# SCH_Photon-Avatar-Headset_2024-04-25.net
KiCad netlist of a schematic drawn in EasyEDA
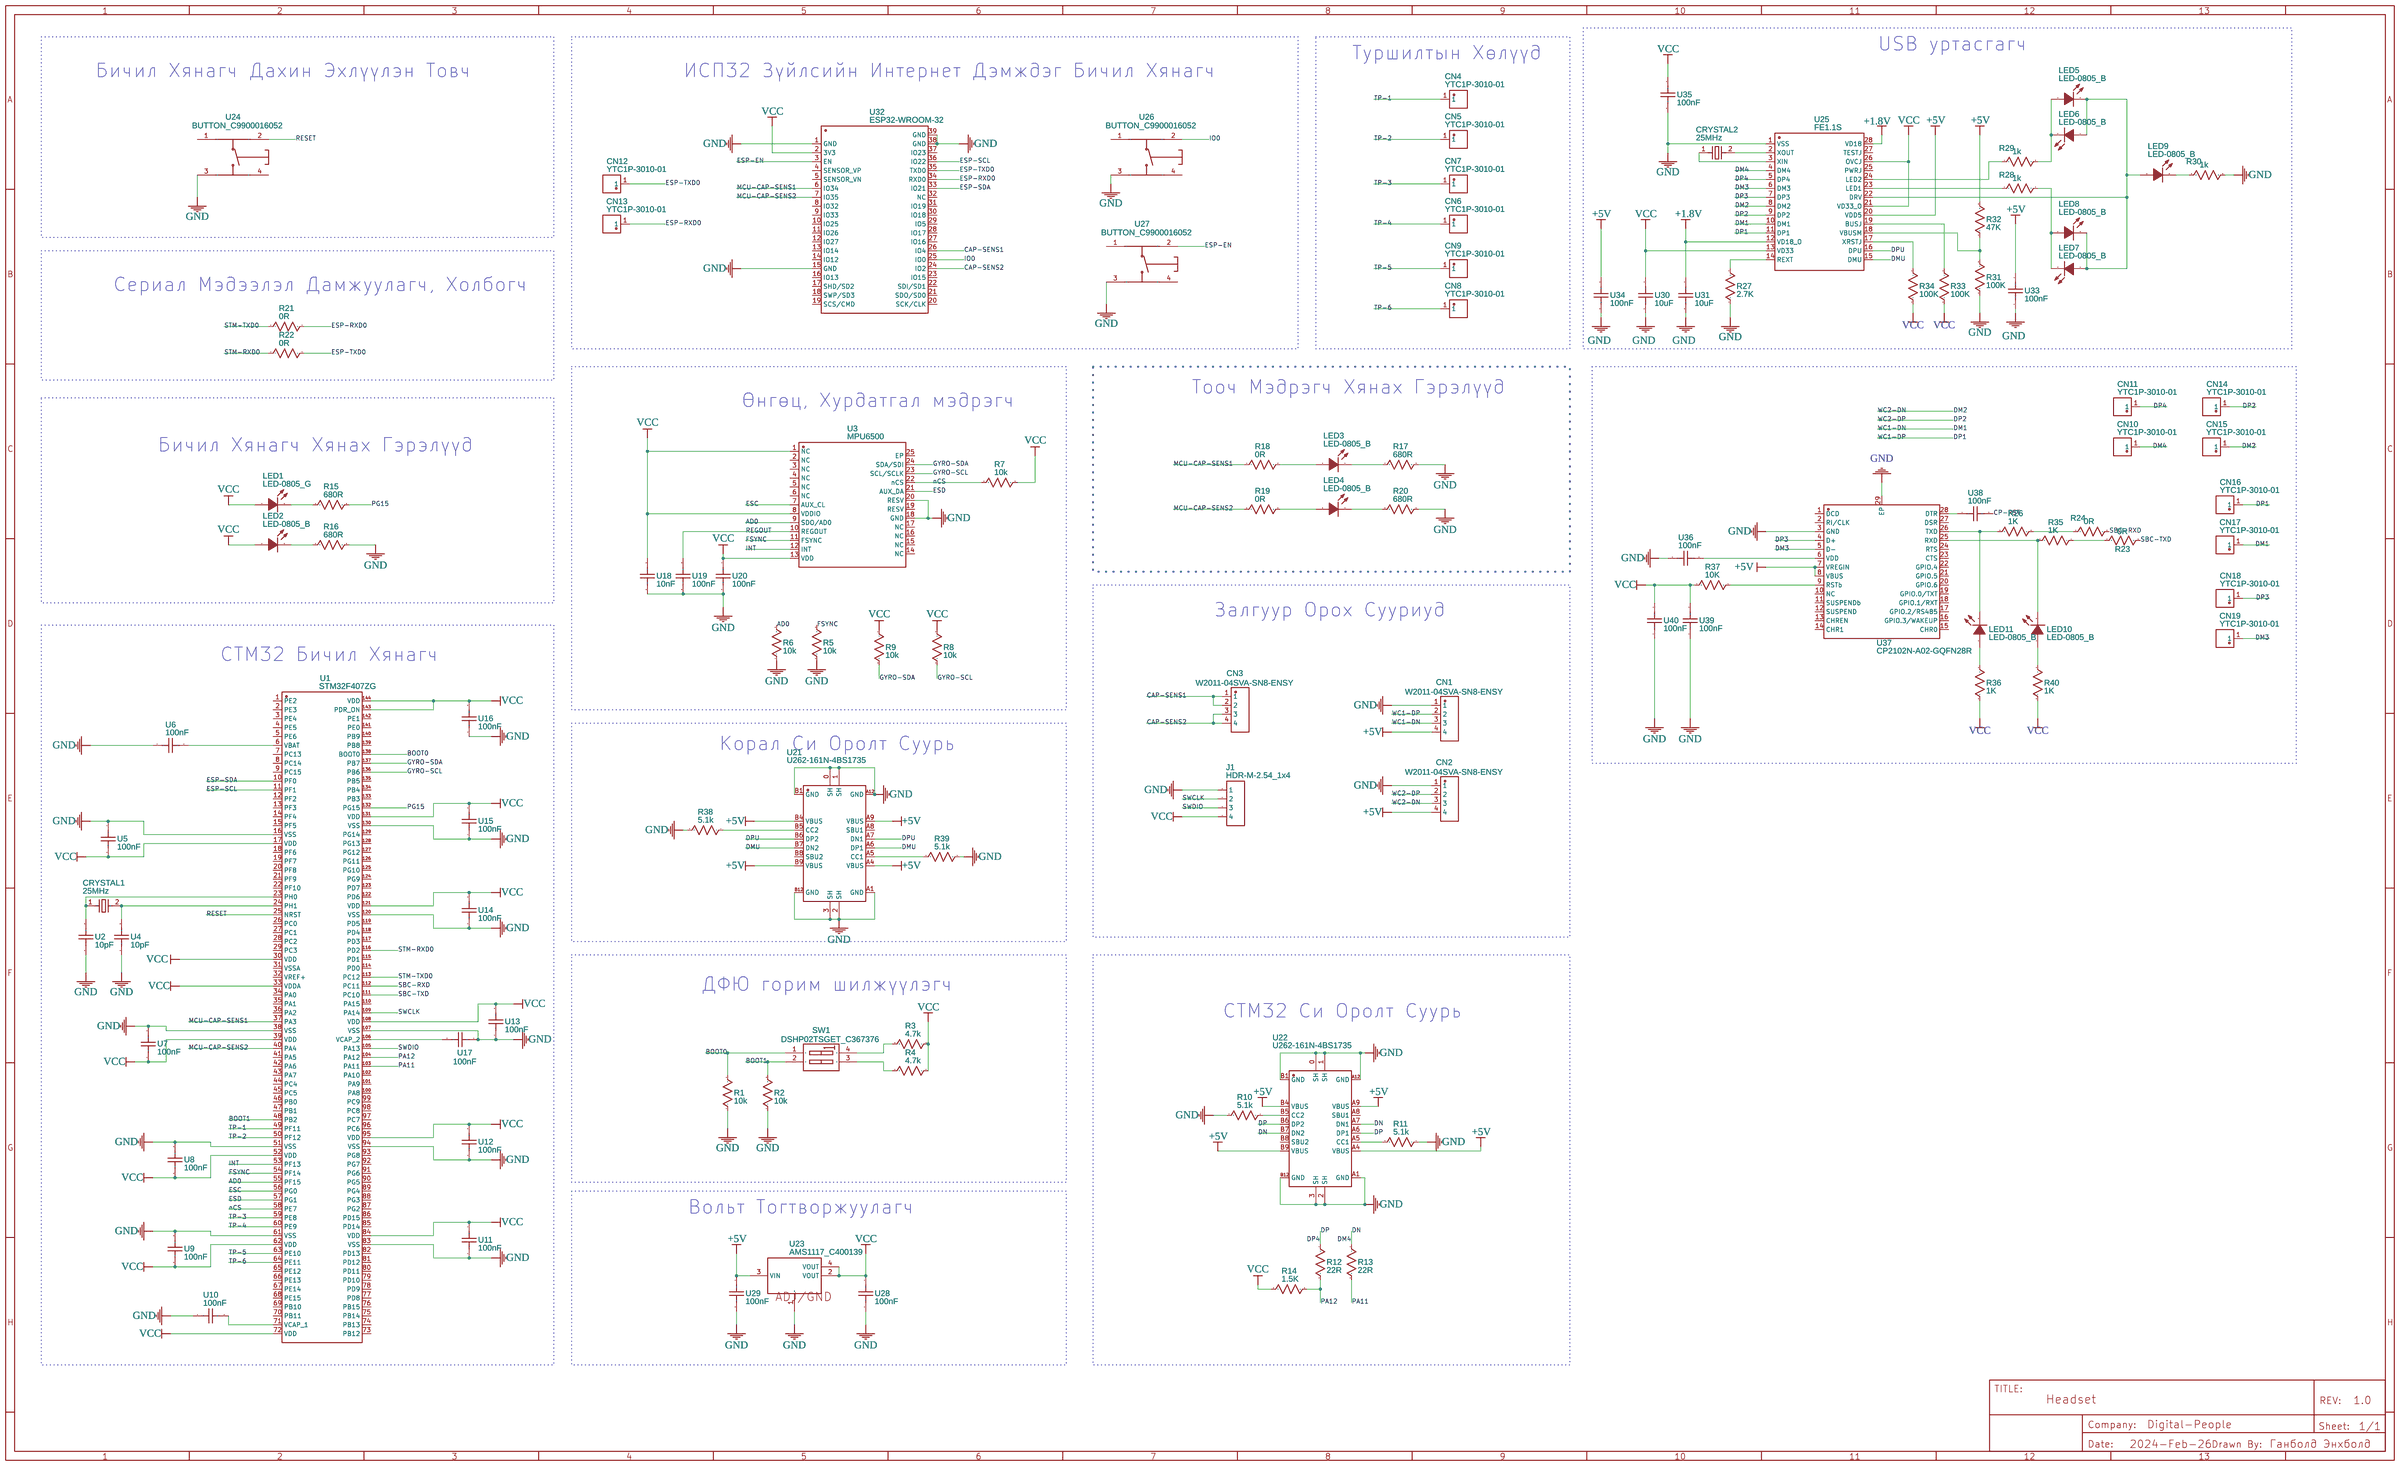
[diagram p0: schematic sheet]

(export (version "E")
  (design (tool "Eeschema 10.0.6"))
  (components
    (comp (ref "CN1") (value "W2011-04SVA-SN8-ENSY") (libsource (lib "") (part "W2011-04SVA-SN8-ENSY")))
    (comp (ref "CN2") (value "W2011-04SVA-SN8-ENSY") (libsource (lib "") (part "W2011-04SVA-SN8-ENSY")))
    (comp (ref "CN3") (value "W2011-04SVA-SN8-ENSY") (libsource (lib "") (part "W2011-04SVA-SN8-ENSY")))
    (comp (ref "CN4")
      (value "YTC1P-3010-01")
      (fields (field (name "Manufacturer") "YIYUAN(怡远)"))
      (libsource (lib "") (part "YTC1P-3010-01"))
    )
    (comp (ref "CN5")
      (value "YTC1P-3010-01")
      (fields (field (name "Manufacturer") "YIYUAN(怡远)"))
      (libsource (lib "") (part "YTC1P-3010-01"))
    )
    (comp (ref "CN6")
      (value "YTC1P-3010-01")
      (fields (field (name "Manufacturer") "YIYUAN(怡远)"))
      (libsource (lib "") (part "YTC1P-3010-01"))
    )
    (comp (ref "CN7")
      (value "YTC1P-3010-01")
      (fields (field (name "Manufacturer") "YIYUAN(怡远)"))
      (libsource (lib "") (part "YTC1P-3010-01"))
    )
    (comp (ref "CN8")
      (value "YTC1P-3010-01")
      (fields (field (name "Manufacturer") "YIYUAN(怡远)"))
      (libsource (lib "") (part "YTC1P-3010-01"))
    )
    (comp (ref "CN9")
      (value "YTC1P-3010-01")
      (fields (field (name "Manufacturer") "YIYUAN(怡远)"))
      (libsource (lib "") (part "YTC1P-3010-01"))
    )
    (comp (ref "CN10")
      (value "YTC1P-3010-01")
      (fields (field (name "Manufacturer") "YIYUAN(怡远)"))
      (libsource (lib "") (part "YTC1P-3010-01_1"))
    )
    (comp (ref "CN11")
      (value "YTC1P-3010-01")
      (fields (field (name "Manufacturer") "YIYUAN(怡远)"))
      (libsource (lib "") (part "YTC1P-3010-01_1"))
    )
    (comp (ref "CN12")
      (value "YTC1P-3010-01")
      (fields (field (name "Manufacturer") "YIYUAN(怡远)"))
      (libsource (lib "") (part "YTC1P-3010-01_1"))
    )
    (comp (ref "CN13")
      (value "YTC1P-3010-01")
      (fields (field (name "Manufacturer") "YIYUAN(怡远)"))
      (libsource (lib "") (part "YTC1P-3010-01_1"))
    )
    (comp (ref "CN14")
      (value "YTC1P-3010-01")
      (fields (field (name "Manufacturer") "YIYUAN(怡远)"))
      (libsource (lib "") (part "YTC1P-3010-01_1"))
    )
    (comp (ref "CN15")
      (value "YTC1P-3010-01")
      (fields (field (name "Manufacturer") "YIYUAN(怡远)"))
      (libsource (lib "") (part "YTC1P-3010-01_1"))
    )
    (comp (ref "CN16")
      (value "YTC1P-3010-01")
      (fields (field (name "Manufacturer") "YIYUAN(怡远)"))
      (libsource (lib "") (part "YTC1P-3010-01_1"))
    )
    (comp (ref "CN17")
      (value "YTC1P-3010-01")
      (fields (field (name "Manufacturer") "YIYUAN(怡远)"))
      (libsource (lib "") (part "YTC1P-3010-01_1"))
    )
    (comp (ref "CN18")
      (value "YTC1P-3010-01")
      (fields (field (name "Manufacturer") "YIYUAN(怡远)"))
      (libsource (lib "") (part "YTC1P-3010-01_1"))
    )
    (comp (ref "CN19")
      (value "YTC1P-3010-01")
      (fields (field (name "Manufacturer") "YIYUAN(怡远)"))
      (libsource (lib "") (part "YTC1P-3010-01_1"))
    )
    (comp (ref "CRYSTAL1")
      (value "25MHz")
      (fields (field (name "Manufacturer Part") "SD2012M00020001") (field (name "Manufacturer") "HUAXIN(华昕)"))
      (libsource (lib "") (part "SD2012M00020001"))
    )
    (comp (ref "CRYSTAL2")
      (value "25MHz")
      (fields (field (name "Manufacturer Part") "SD2012M00020001") (field (name "Manufacturer") "HUAXIN(华昕)"))
      (libsource (lib "") (part "SD2012M00020001"))
    )
    (comp (ref "J1") (value "HDR-M-2.54_1x4") (libsource (lib "") (part "HDR-M-2.54_1x4")))
    (comp (ref "LED1")
      (value "LED-0805_G")
      (fields (field (name "Manufacturer Part") "NCD0805G1") (field (name "Manufacturer") "国星光电"))
      (libsource (lib "") (part "LED-0805_G"))
    )
    (comp (ref "LED2")
      (value "LED-0805_B")
      (fields (field (name "Manufacturer Part") "D-B080508B1-KS2") (field (name "Manufacturer") "方舟 ARKLED"))
      (libsource (lib "") (part "LED-0805_B_1"))
    )
    (comp (ref "LED3")
      (value "LED-0805_B")
      (fields (field (name "Manufacturer Part") "D-B080508B1-KS2") (field (name "Manufacturer") "方舟 ARKLED"))
      (libsource (lib "") (part "LED-0805_B_1"))
    )
    (comp (ref "LED4")
      (value "LED-0805_B")
      (fields (field (name "Manufacturer Part") "D-B080508B1-KS2") (field (name "Manufacturer") "方舟 ARKLED"))
      (libsource (lib "") (part "LED-0805_B_1"))
    )
    (comp (ref "LED5")
      (value "LED-0805_B")
      (fields (field (name "Manufacturer Part") "D-B080508B1-KS2") (field (name "Manufacturer") "方舟 ARKLED"))
      (libsource (lib "") (part "LED-0805_B_1"))
    )
    (comp (ref "LED6")
      (value "LED-0805_B")
      (fields (field (name "Manufacturer Part") "D-B080508B1-KS2") (field (name "Manufacturer") "方舟 ARKLED"))
      (libsource (lib "") (part "LED-0805_B_2"))
    )
    (comp (ref "LED7")
      (value "LED-0805_B")
      (fields (field (name "Manufacturer Part") "D-B080508B1-KS2") (field (name "Manufacturer") "方舟 ARKLED"))
      (libsource (lib "") (part "LED-0805_B_2"))
    )
    (comp (ref "LED8")
      (value "LED-0805_B")
      (fields (field (name "Manufacturer Part") "D-B080508B1-KS2") (field (name "Manufacturer") "方舟 ARKLED"))
      (libsource (lib "") (part "LED-0805_B_1"))
    )
    (comp (ref "LED9")
      (value "LED-0805_B")
      (fields (field (name "Manufacturer Part") "D-B080508B1-KS2") (field (name "Manufacturer") "方舟 ARKLED"))
      (libsource (lib "") (part "LED-0805_B_1"))
    )
    (comp (ref "LED10")
      (value "LED-0805_B")
      (fields (field (name "Manufacturer Part") "D-B080508B1-KS2") (field (name "Manufacturer") "方舟 ARKLED"))
      (libsource (lib "") (part "LED-0805_B"))
    )
    (comp (ref "LED11")
      (value "LED-0805_B")
      (fields (field (name "Manufacturer Part") "D-B080508B1-KS2") (field (name "Manufacturer") "方舟 ARKLED"))
      (libsource (lib "") (part "LED-0805_B"))
    )
    (comp (ref "R1") (value "10k") (libsource (lib "") (part "R_0805_US_2")))
    (comp (ref "R2") (value "10k") (libsource (lib "") (part "R_0805_US_2")))
    (comp (ref "R3") (value "4.7k") (libsource (lib "") (part "R_0805_US_3")))
    (comp (ref "R4") (value "4.7k") (libsource (lib "") (part "R_0805_US_3")))
    (comp (ref "R5") (value "10k") (libsource (lib "") (part "R_0805_US_2")))
    (comp (ref "R6") (value "10k") (libsource (lib "") (part "R_0805_US_2")))
    (comp (ref "R7") (value "10k") (libsource (lib "") (part "R_0805_US_3")))
    (comp (ref "R8") (value "10k") (libsource (lib "") (part "R_0805_US_1")))
    (comp (ref "R9") (value "10k") (libsource (lib "") (part "R_0805_US_1")))
    (comp (ref "R10") (value "5.1k") (libsource (lib "") (part "R_0805_US_3")))
    (comp (ref "R11") (value "5.1k") (libsource (lib "") (part "R_0805_US_3")))
    (comp (ref "R12") (value "22R") (libsource (lib "") (part "R_0805_US_1")))
    (comp (ref "R13") (value "22R") (libsource (lib "") (part "R_0805_US_1")))
    (comp (ref "R14") (value "1.5K") (libsource (lib "") (part "R_0805_US")))
    (comp (ref "R15") (value "680R") (libsource (lib "") (part "R_0805_US")))
    (comp (ref "R16") (value "680R") (libsource (lib "") (part "R_0805_US")))
    (comp (ref "R17") (value "680R") (libsource (lib "") (part "R_0805_US")))
    (comp (ref "R18") (value "0R") (libsource (lib "") (part "R_0805_US")))
    (comp (ref "R19") (value "0R") (libsource (lib "") (part "R_0805_US")))
    (comp (ref "R20") (value "680R") (libsource (lib "") (part "R_0805_US")))
    (comp (ref "R21") (value "0R") (libsource (lib "") (part "R_0805_US")))
    (comp (ref "R22") (value "0R") (libsource (lib "") (part "R_0805_US")))
    (comp (ref "R23") (value "0R") (libsource (lib "") (part "R_0805_US")))
    (comp (ref "R24") (value "0R") (libsource (lib "") (part "R_0805_US")))
    (comp (ref "R26") (value "1K") (libsource (lib "") (part "R_0805_US_3")))
    (comp (ref "R27") (value "2.7K") (libsource (lib "") (part "R_0805_US_2")))
    (comp (ref "R28") (value "1k") (libsource (lib "") (part "R_0805_US")))
    (comp (ref "R29") (value "1k") (libsource (lib "") (part "R_0805_US")))
    (comp (ref "R30") (value "1k") (libsource (lib "") (part "R_0805_US")))
    (comp (ref "R31") (value "100K") (libsource (lib "") (part "R_0805_US_2")))
    (comp (ref "R32") (value "47K") (libsource (lib "") (part "R_0805_US_2")))
    (comp (ref "R33") (value "100K") (libsource (lib "") (part "R_0805_US_1")))
    (comp (ref "R34") (value "100K") (libsource (lib "") (part "R_0805_US_1")))
    (comp (ref "R35") (value "1K") (libsource (lib "") (part "R_0805_US_3")))
    (comp (ref "R36") (value "1K") (libsource (lib "") (part "R_0805_US_2")))
    (comp (ref "R37") (value "10K") (libsource (lib "") (part "R_0805_US_3")))
    (comp (ref "R38") (value "5.1k") (libsource (lib "") (part "R_0805_US_3")))
    (comp (ref "R39") (value "5.1k") (libsource (lib "") (part "R_0805_US_3")))
    (comp (ref "R40") (value "1K") (libsource (lib "") (part "R_0805_US_2")))
    (comp (ref "SW1")
      (value "DSHP02TSGET_C367376")
      (fields (field (name "Manufacturer Part") "DSHP02TSGER") (field (name "Manufacturer") "YE"))
      (libsource (lib "") (part "DSHP02TSGET_C367376"))
    )
    (comp (ref "U1") (value "STM32F407ZG") (libsource (lib "") (part "STM32F407ZG")))
    (comp (ref "U2")
      (value "10pF")
      (fields
        (field (name "Manufacturer Part") "0805N220J500CT-C")
        (field (name "Manufacturer") "Walsin(华新科)")
      )
      (libsource (lib "") (part "0805N220J500CT-C_1"))
    )
    (comp (ref "U3")
      (value "MPU6500")
      (fields
        (field (name "Manufacturer Part") "MPU-6500")
        (field (name "Manufacturer") "TDK InvenSense(应美盛)")
      )
      (libsource (lib "") (part "MPU6500"))
    )
    (comp (ref "U4")
      (value "10pF")
      (fields
        (field (name "Manufacturer Part") "0805N220J500CT-C")
        (field (name "Manufacturer") "Walsin(华新科)")
      )
      (libsource (lib "") (part "0805N220J500CT-C_1"))
    )
    (comp (ref "U5")
      (value "100nF")
      (fields
        (field (name "Manufacturer Part") "0805N220J500CT-C")
        (field (name "Manufacturer") "Walsin(华新科)")
      )
      (libsource (lib "") (part "0805N220J500CT-C"))
    )
    (comp (ref "U6")
      (value "100nF")
      (fields
        (field (name "Manufacturer Part") "0805N220J500CT-C")
        (field (name "Manufacturer") "Walsin(华新科)")
      )
      (libsource (lib "") (part "0805N220J500CT-C_2"))
    )
    (comp (ref "U7")
      (value "100nF")
      (fields
        (field (name "Manufacturer Part") "0805N220J500CT-C")
        (field (name "Manufacturer") "Walsin(华新科)")
      )
      (libsource (lib "") (part "0805N220J500CT-C"))
    )
    (comp (ref "U8")
      (value "100nF")
      (fields
        (field (name "Manufacturer Part") "0805N220J500CT-C")
        (field (name "Manufacturer") "Walsin(华新科)")
      )
      (libsource (lib "") (part "0805N220J500CT-C"))
    )
    (comp (ref "U9")
      (value "100nF")
      (fields
        (field (name "Manufacturer Part") "0805N220J500CT-C")
        (field (name "Manufacturer") "Walsin(华新科)")
      )
      (libsource (lib "") (part "0805N220J500CT-C"))
    )
    (comp (ref "U10")
      (value "100nF")
      (fields
        (field (name "Manufacturer Part") "0805N220J500CT-C")
        (field (name "Manufacturer") "Walsin(华新科)")
      )
      (libsource (lib "") (part "0805N220J500CT-C_2"))
    )
    (comp (ref "U11")
      (value "100nF")
      (fields
        (field (name "Manufacturer Part") "0805N220J500CT-C")
        (field (name "Manufacturer") "Walsin(华新科)")
      )
      (libsource (lib "") (part "0805N220J500CT-C_1"))
    )
    (comp (ref "U12")
      (value "100nF")
      (fields
        (field (name "Manufacturer Part") "0805N220J500CT-C")
        (field (name "Manufacturer") "Walsin(华新科)")
      )
      (libsource (lib "") (part "0805N220J500CT-C_1"))
    )
    (comp (ref "U13")
      (value "100nF")
      (fields
        (field (name "Manufacturer Part") "0805N220J500CT-C")
        (field (name "Manufacturer") "Walsin(华新科)")
      )
      (libsource (lib "") (part "0805N220J500CT-C_1"))
    )
    (comp (ref "U14")
      (value "100nF")
      (fields
        (field (name "Manufacturer Part") "0805N220J500CT-C")
        (field (name "Manufacturer") "Walsin(华新科)")
      )
      (libsource (lib "") (part "0805N220J500CT-C_1"))
    )
    (comp (ref "U15")
      (value "100nF")
      (fields
        (field (name "Manufacturer Part") "0805N220J500CT-C")
        (field (name "Manufacturer") "Walsin(华新科)")
      )
      (libsource (lib "") (part "0805N220J500CT-C_1"))
    )
    (comp (ref "U16")
      (value "100nF")
      (fields
        (field (name "Manufacturer Part") "0805N220J500CT-C")
        (field (name "Manufacturer") "Walsin(华新科)")
      )
      (libsource (lib "") (part "0805N220J500CT-C_1"))
    )
    (comp (ref "U17")
      (value "100nF")
      (fields
        (field (name "Manufacturer Part") "0805N220J500CT-C")
        (field (name "Manufacturer") "Walsin(华新科)")
      )
      (libsource (lib "") (part "0805N220J500CT-C_3"))
    )
    (comp (ref "U18")
      (value "10nF")
      (fields
        (field (name "Manufacturer Part") "0805N220J500CT-C")
        (field (name "Manufacturer") "Walsin(华新科)")
      )
      (libsource (lib "") (part "0805N220J500CT-C"))
    )
    (comp (ref "U19")
      (value "100nF")
      (fields
        (field (name "Manufacturer Part") "0805N220J500CT-C")
        (field (name "Manufacturer") "Walsin(华新科)")
      )
      (libsource (lib "") (part "0805N220J500CT-C"))
    )
    (comp (ref "U20")
      (value "100nF")
      (fields
        (field (name "Manufacturer Part") "0805N220J500CT-C")
        (field (name "Manufacturer") "Walsin(华新科)")
      )
      (libsource (lib "") (part "0805N220J500CT-C"))
    )
    (comp (ref "U21")
      (value "U262-161N-4BS1735")
      (fields (field (name "Manufacturer") "XKB Connectivity(中国星坤)"))
      (libsource (lib "") (part "U262-161N-4BS1735"))
    )
    (comp (ref "U22")
      (value "U262-161N-4BS1735")
      (fields (field (name "Manufacturer") "XKB Connectivity(中国星坤)"))
      (libsource (lib "") (part "U262-161N-4BS1735"))
    )
    (comp (ref "U23")
      (value "AMS1117_C400139")
      (fields
        (field (name "Manufacturer Part") "AMS1117-T33")
        (field (name "Manufacturer") "UNI-SEMI(宇力半导体)")
      )
      (libsource (lib "") (part "AMS1117_C400139"))
    )
    (comp (ref "U24")
      (value "BUTTON_C9900016052")
      (fields (field (name "Manufacturer Part") "button"))
      (libsource (lib "") (part "BUTTON_C9900016052"))
    )
    (comp (ref "U25")
      (value "FE1.1S")
      (fields (field (name "Manufacturer Part") "FE1.1S-BSOP28BCN") (field (name "Manufacturer") "TERMINUS"))
      (libsource (lib "") (part "FE1.1S"))
    )
    (comp (ref "U26")
      (value "BUTTON_C9900016052")
      (fields (field (name "Manufacturer Part") "button"))
      (libsource (lib "") (part "BUTTON_C9900016052"))
    )
    (comp (ref "U27")
      (value "BUTTON_C9900016052")
      (fields (field (name "Manufacturer Part") "button"))
      (libsource (lib "") (part "BUTTON_C9900016052"))
    )
    (comp (ref "U28")
      (value "100nF")
      (fields
        (field (name "Manufacturer Part") "0805N220J500CT-C")
        (field (name "Manufacturer") "Walsin(华新科)")
      )
      (libsource (lib "") (part "0805N220J500CT-C"))
    )
    (comp (ref "U29")
      (value "100nF")
      (fields
        (field (name "Manufacturer Part") "0805N220J500CT-C")
        (field (name "Manufacturer") "Walsin(华新科)")
      )
      (libsource (lib "") (part "0805N220J500CT-C"))
    )
    (comp (ref "U30")
      (value "10uF")
      (fields
        (field (name "Manufacturer Part") "0805N220J500CT-C")
        (field (name "Manufacturer") "Walsin(华新科)")
      )
      (libsource (lib "") (part "0805N220J500CT-C"))
    )
    (comp (ref "U31")
      (value "10uF")
      (fields
        (field (name "Manufacturer Part") "0805N220J500CT-C")
        (field (name "Manufacturer") "Walsin(华新科)")
      )
      (libsource (lib "") (part "0805N220J500CT-C"))
    )
    (comp (ref "U32")
      (value "ESP32-WROOM-32")
      (fields
        (field (name "Manufacturer Part") "ESP32-WROOM-32-N4")
        (field (name "Manufacturer") "ESPRESSIF(乐鑫)")
      )
      (libsource (lib "") (part "ESP32-WROOM-32"))
    )
    (comp (ref "U33")
      (value "100nF")
      (fields
        (field (name "Manufacturer Part") "0805N220J500CT-C")
        (field (name "Manufacturer") "Walsin(华新科)")
      )
      (libsource (lib "") (part "0805N220J500CT-C"))
    )
    (comp (ref "U34")
      (value "100nF")
      (fields
        (field (name "Manufacturer Part") "0805N220J500CT-C")
        (field (name "Manufacturer") "Walsin(华新科)")
      )
      (libsource (lib "") (part "0805N220J500CT-C"))
    )
    (comp (ref "U35")
      (value "100nF")
      (fields
        (field (name "Manufacturer Part") "0805N220J500CT-C")
        (field (name "Manufacturer") "Walsin(华新科)")
      )
      (libsource (lib "") (part "0805N220J500CT-C"))
    )
    (comp (ref "U36")
      (value "100nF")
      (fields
        (field (name "Manufacturer Part") "0805N220J500CT-C")
        (field (name "Manufacturer") "Walsin(华新科)")
      )
      (libsource (lib "") (part "0805N220J500CT-C_2"))
    )
    (comp (ref "U37")
      (value "CP2102N-A02-GQFN28R")
      (fields (field (name "Manufacturer") "SKYWORKS/SILICON LABS(芯科)"))
      (libsource (lib "") (part "CP2102N-A02-GQFN28R"))
    )
    (comp (ref "U38")
      (value "100nF")
      (fields
        (field (name "Manufacturer Part") "0805N220J500CT-C")
        (field (name "Manufacturer") "Walsin(华新科)")
      )
      (libsource (lib "") (part "0805N220J500CT-C_2"))
    )
    (comp (ref "U39")
      (value "100nF")
      (fields
        (field (name "Manufacturer Part") "0805N220J500CT-C")
        (field (name "Manufacturer") "Walsin(华新科)")
      )
      (libsource (lib "") (part "0805N220J500CT-C_1"))
    )
    (comp (ref "U40")
      (value "100nF")
      (fields
        (field (name "Manufacturer Part") "0805N220J500CT-C")
        (field (name "Manufacturer") "Walsin(华新科)")
      )
      (libsource (lib "") (part "0805N220J500CT-C_1"))
    )
  )
  (nets
    (net (code "1") (name "+1.8V") (class "Default")
      (node (ref "U25") (pin "12") (pinfunction "VD18_O_12") (pintype "unspecified"))
      (node (ref "U25") (pin "28") (pinfunction "VD18_28") (pintype "unspecified"))
      (node (ref "U31") (pin "1") (pinfunction "1_1") (pintype "unspecified"))
    )
    (net (code "2") (name "+5V") (class "Default")
      (node (ref "CN1") (pin "4") (pinfunction "4_4") (pintype "unspecified"))
      (node (ref "CN2") (pin "4") (pinfunction "4_4") (pintype "unspecified"))
      (node (ref "R32") (pin "2") (pinfunction "2_2") (pintype "unspecified"))
      (node (ref "U21") (pin "A4") (pinfunction "VBUS_A4") (pintype "unspecified"))
      (node (ref "U21") (pin "A9") (pinfunction "VBUS_A9") (pintype "unspecified"))
      (node (ref "U21") (pin "B4") (pinfunction "VBUS_B4") (pintype "unspecified"))
      (node (ref "U21") (pin "B9") (pinfunction "VBUS_B9") (pintype "unspecified"))
      (node (ref "U22") (pin "A4") (pinfunction "VBUS_A4") (pintype "unspecified"))
      (node (ref "U22") (pin "A9") (pinfunction "VBUS_A9") (pintype "unspecified"))
      (node (ref "U22") (pin "B4") (pinfunction "VBUS_B4") (pintype "unspecified"))
      (node (ref "U22") (pin "B9") (pinfunction "VBUS_B9") (pintype "unspecified"))
      (node (ref "U23") (pin "3") (pinfunction "VIN_3") (pintype "passive"))
      (node (ref "U25") (pin "20") (pinfunction "VDD5_20") (pintype "unspecified"))
      (node (ref "U29") (pin "1") (pinfunction "1_1") (pintype "unspecified"))
      (node (ref "U33") (pin "1") (pinfunction "1_1") (pintype "unspecified"))
      (node (ref "U34") (pin "1") (pinfunction "1_1") (pintype "unspecified"))
      (node (ref "U37") (pin "7") (pinfunction "VREGIN_7") (pintype "unspecified"))
      (node (ref "U37") (pin "8") (pinfunction "VBUS_8") (pintype "unspecified"))
    )
    (net (code "3") (name "/AD0") (class "Default")
      (node (ref "R6") (pin "2") (pinfunction "2_2") (pintype "unspecified"))
      (node (ref "U1") (pin "55") (pinfunction "PF15_55") (pintype "unspecified"))
      (node (ref "U3") (pin "9") (pinfunction "SDO/AD0_9") (pintype "unspecified"))
    )
    (net (code "4") (name "/BOOT0") (class "Default")
      (node (ref "R1") (pin "2") (pinfunction "2_2") (pintype "unspecified"))
      (node (ref "SW1") (pin "1") (pinfunction "A1_1") (pintype "input"))
      (node (ref "U1") (pin "138") (pinfunction "BOOT0_138") (pintype "unspecified"))
    )
    (net (code "5") (name "/BOOT1") (class "Default")
      (node (ref "R2") (pin "2") (pinfunction "2_2") (pintype "unspecified"))
      (node (ref "SW1") (pin "2") (pinfunction "A2_2") (pintype "input"))
      (node (ref "U1") (pin "48") (pinfunction "PB2_48") (pintype "unspecified"))
    )
    (net (code "6") (name "/CAP-SENS1") (class "Default")
      (node (ref "CN3") (pin "1") (pinfunction "1_1") (pintype "unspecified"))
      (node (ref "CN3") (pin "2") (pinfunction "2_2") (pintype "unspecified"))
      (node (ref "U32") (pin "26") (pinfunction "IO4_26") (pintype "unspecified"))
    )
    (net (code "7") (name "/CAP-SENS2") (class "Default")
      (node (ref "CN3") (pin "3") (pinfunction "3_3") (pintype "unspecified"))
      (node (ref "CN3") (pin "4") (pinfunction "4_4") (pintype "unspecified"))
      (node (ref "U32") (pin "24") (pinfunction "IO2_24") (pintype "unspecified"))
    )
    (net (code "8") (name "/CP-RST") (class "Default")
      (node (ref "U38") (pin "2") (pinfunction "2_2") (pintype "unspecified"))
    )
    (net (code "9") (name "/DM1") (class "Default")
      (node (ref "CN1") (pin "3") (pinfunction "3_3") (pintype "unspecified"))
      (node (ref "CN17") (pin "1") (pinfunction "1_1") (pintype "unspecified"))
      (node (ref "U25") (pin "10") (pinfunction "DM1_10") (pintype "unspecified"))
    )
    (net (code "10") (name "/DM2") (class "Default")
      (node (ref "CN15") (pin "1") (pinfunction "1_1") (pintype "unspecified"))
      (node (ref "CN2") (pin "3") (pinfunction "3_3") (pintype "unspecified"))
      (node (ref "U25") (pin "8") (pinfunction "DM2_8") (pintype "unspecified"))
    )
    (net (code "11") (name "/DM3") (class "Default")
      (node (ref "CN19") (pin "1") (pinfunction "1_1") (pintype "unspecified"))
      (node (ref "U25") (pin "6") (pinfunction "DM3_6") (pintype "unspecified"))
      (node (ref "U37") (pin "5") (pinfunction "D-_5") (pintype "unspecified"))
    )
    (net (code "12") (name "/DM4") (class "Default")
      (node (ref "CN10") (pin "1") (pinfunction "1_1") (pintype "unspecified"))
      (node (ref "R13") (pin "1") (pinfunction "1_1") (pintype "unspecified"))
      (node (ref "U22") (pin "A7") (pinfunction "DN1_A7") (pintype "unspecified"))
      (node (ref "U22") (pin "B7") (pinfunction "DN2_B7") (pintype "unspecified"))
      (node (ref "U25") (pin "4") (pinfunction "DM4_4") (pintype "unspecified"))
    )
    (net (code "13") (name "/DMU") (class "Default")
      (node (ref "U21") (pin "A6") (pinfunction "DP1_A6") (pintype "unspecified"))
      (node (ref "U21") (pin "B7") (pinfunction "DN2_B7") (pintype "unspecified"))
      (node (ref "U25") (pin "15") (pinfunction "DMU_15") (pintype "unspecified"))
    )
    (net (code "14") (name "/DP") (class "Default")
      (node (ref "CN11") (pin "1") (pinfunction "1_1") (pintype "unspecified"))
      (node (ref "R12") (pin "1") (pinfunction "1_1") (pintype "unspecified"))
      (node (ref "U22") (pin "A6") (pinfunction "DP1_A6") (pintype "unspecified"))
      (node (ref "U22") (pin "B6") (pinfunction "DP2_B6") (pintype "unspecified"))
      (node (ref "U25") (pin "5") (pinfunction "DP4_5") (pintype "unspecified"))
    )
    (net (code "15") (name "/DP1") (class "Default")
      (node (ref "CN1") (pin "2") (pinfunction "2_2") (pintype "unspecified"))
      (node (ref "CN16") (pin "1") (pinfunction "1_1") (pintype "unspecified"))
      (node (ref "U25") (pin "11") (pinfunction "DP1_11") (pintype "unspecified"))
    )
    (net (code "16") (name "/DP2") (class "Default")
      (node (ref "CN14") (pin "1") (pinfunction "1_1") (pintype "unspecified"))
      (node (ref "CN2") (pin "2") (pinfunction "2_2") (pintype "unspecified"))
      (node (ref "U25") (pin "9") (pinfunction "DP2_9") (pintype "unspecified"))
    )
    (net (code "17") (name "/DP3") (class "Default")
      (node (ref "CN18") (pin "1") (pinfunction "1_1") (pintype "unspecified"))
      (node (ref "U25") (pin "7") (pinfunction "DP3_7") (pintype "unspecified"))
      (node (ref "U37") (pin "4") (pinfunction "D+_4") (pintype "unspecified"))
    )
    (net (code "18") (name "/DPU") (class "Default")
      (node (ref "U21") (pin "A7") (pinfunction "DN1_A7") (pintype "unspecified"))
      (node (ref "U21") (pin "B6") (pinfunction "DP2_B6") (pintype "unspecified"))
      (node (ref "U25") (pin "16") (pinfunction "DPU_16") (pintype "unspecified"))
    )
    (net (code "19") (name "/ESC") (class "Default")
      (node (ref "U1") (pin "56") (pinfunction "PG0_56") (pintype "unspecified"))
      (node (ref "U3") (pin "7") (pinfunction "AUX_CL_7") (pintype "unspecified"))
    )
    (net (code "20") (name "/ESD") (class "Default")
      (node (ref "U1") (pin "57") (pinfunction "PG1_57") (pintype "unspecified"))
      (node (ref "U3") (pin "21") (pinfunction "AUX_DA_21") (pintype "unspecified"))
    )
    (net (code "21") (name "/ESP-EN") (class "Default")
      (node (ref "U27") (pin "2") (pinfunction "2_2") (pintype "unspecified"))
      (node (ref "U32") (pin "3") (pinfunction "EN_3") (pintype "unspecified"))
    )
    (net (code "22") (name "/ESP-RXD0") (class "Default")
      (node (ref "CN13") (pin "1") (pinfunction "1_1") (pintype "unspecified"))
      (node (ref "R21") (pin "2") (pinfunction "2_2") (pintype "unspecified"))
      (node (ref "U32") (pin "34") (pinfunction "RXD0_34") (pintype "unspecified"))
    )
    (net (code "23") (name "/ESP-SCL") (class "Default")
      (node (ref "U1") (pin "11") (pinfunction "PF1_11") (pintype "unspecified"))
      (node (ref "U32") (pin "36") (pinfunction "IO22_36") (pintype "unspecified"))
    )
    (net (code "24") (name "/ESP-SDA") (class "Default")
      (node (ref "U1") (pin "10") (pinfunction "PF0_10") (pintype "unspecified"))
      (node (ref "U32") (pin "33") (pinfunction "IO21_33") (pintype "unspecified"))
    )
    (net (code "25") (name "/ESP-TXD0") (class "Default")
      (node (ref "CN12") (pin "1") (pinfunction "1_1") (pintype "unspecified"))
      (node (ref "R22") (pin "2") (pinfunction "2_2") (pintype "unspecified"))
      (node (ref "U32") (pin "35") (pinfunction "TXD0_35") (pintype "unspecified"))
    )
    (net (code "26") (name "/FSYNC") (class "Default")
      (node (ref "R5") (pin "2") (pinfunction "2_2") (pintype "unspecified"))
      (node (ref "U1") (pin "54") (pinfunction "PF14_54") (pintype "unspecified"))
      (node (ref "U3") (pin "11") (pinfunction "FSYNC_11") (pintype "unspecified"))
    )
    (net (code "27") (name "/GYRO-SCL") (class "Default")
      (node (ref "R8") (pin "2") (pinfunction "2_2") (pintype "unspecified"))
      (node (ref "U1") (pin "136") (pinfunction "PB6_136") (pintype "unspecified"))
      (node (ref "U3") (pin "23") (pinfunction "SCL/SCLK_23") (pintype "unspecified"))
    )
    (net (code "28") (name "/GYRO-SDA") (class "Default")
      (node (ref "R9") (pin "2") (pinfunction "2_2") (pintype "unspecified"))
      (node (ref "U1") (pin "137") (pinfunction "PB7_137") (pintype "unspecified"))
      (node (ref "U3") (pin "24") (pinfunction "SDA/SDI_24") (pintype "unspecified"))
    )
    (net (code "29") (name "/INT") (class "Default")
      (node (ref "U1") (pin "53") (pinfunction "PF13_53") (pintype "unspecified"))
      (node (ref "U3") (pin "12") (pinfunction "INT_12") (pintype "unspecified"))
    )
    (net (code "30") (name "/IO0") (class "Default")
      (node (ref "U26") (pin "2") (pinfunction "2_2") (pintype "unspecified"))
      (node (ref "U32") (pin "25") (pinfunction "IO0_25") (pintype "unspecified"))
    )
    (net (code "31") (name "/MCU-CAP-SENS1") (class "Default")
      (node (ref "R18") (pin "1") (pinfunction "1_1") (pintype "unspecified"))
      (node (ref "U1") (pin "37") (pinfunction "PA3_37") (pintype "unspecified"))
      (node (ref "U32") (pin "6") (pinfunction "IO34_6") (pintype "unspecified"))
    )
    (net (code "32") (name "/MCU-CAP-SENS2") (class "Default")
      (node (ref "R19") (pin "1") (pinfunction "1_1") (pintype "unspecified"))
      (node (ref "U1") (pin "40") (pinfunction "PA4_40") (pintype "unspecified"))
      (node (ref "U32") (pin "7") (pinfunction "IO35_7") (pintype "unspecified"))
    )
    (net (code "33") (name "/PA11") (class "Default")
      (node (ref "R13") (pin "2") (pinfunction "2_2") (pintype "unspecified"))
      (node (ref "U1") (pin "103") (pinfunction "PA11_103") (pintype "unspecified"))
    )
    (net (code "34") (name "/PA12") (class "Default")
      (node (ref "R12") (pin "2") (pinfunction "2_2") (pintype "unspecified"))
      (node (ref "R14") (pin "2") (pinfunction "2_2") (pintype "unspecified"))
      (node (ref "U1") (pin "104") (pinfunction "PA12_104") (pintype "unspecified"))
    )
    (net (code "35") (name "/PG15") (class "Default")
      (node (ref "R15") (pin "2") (pinfunction "2_2") (pintype "unspecified"))
      (node (ref "U1") (pin "132") (pinfunction "PG15_132") (pintype "unspecified"))
    )
    (net (code "36") (name "/REGOUT") (class "Default")
      (node (ref "U19") (pin "1") (pinfunction "1_1") (pintype "unspecified"))
      (node (ref "U3") (pin "10") (pinfunction "REGOUT_10") (pintype "unspecified"))
    )
    (net (code "37") (name "/RESET") (class "Default")
      (node (ref "U1") (pin "25") (pinfunction "NRST_25") (pintype "unspecified"))
      (node (ref "U24") (pin "2") (pinfunction "2_2") (pintype "unspecified"))
    )
    (net (code "38") (name "/SBC-RXD") (class "Default")
      (node (ref "R24") (pin "2") (pinfunction "2_2") (pintype "unspecified"))
      (node (ref "U1") (pin "112") (pinfunction "PC11_112") (pintype "unspecified"))
    )
    (net (code "39") (name "/SBC-TXD") (class "Default")
      (node (ref "R23") (pin "2") (pinfunction "2_2") (pintype "unspecified"))
      (node (ref "U1") (pin "111") (pinfunction "PC10_111") (pintype "unspecified"))
    )
    (net (code "40") (name "/STM-RXD0") (class "Default")
      (node (ref "R22") (pin "1") (pinfunction "1_1") (pintype "unspecified"))
      (node (ref "U1") (pin "116") (pinfunction "PD2_116") (pintype "unspecified"))
    )
    (net (code "41") (name "/STM-TXD0") (class "Default")
      (node (ref "R21") (pin "1") (pinfunction "1_1") (pintype "unspecified"))
      (node (ref "U1") (pin "113") (pinfunction "PC12_113") (pintype "unspecified"))
    )
    (net (code "42") (name "/SWCLK") (class "Default")
      (node (ref "J1") (pin "2") (pinfunction "2_2") (pintype "unspecified"))
      (node (ref "U1") (pin "109") (pinfunction "PA14_109") (pintype "unspecified"))
    )
    (net (code "43") (name "/SWDIO") (class "Default")
      (node (ref "J1") (pin "3") (pinfunction "3_3") (pintype "unspecified"))
      (node (ref "U1") (pin "105") (pinfunction "PA13_105") (pintype "unspecified"))
    )
    (net (code "44") (name "/TP-1") (class "Default")
      (node (ref "CN4") (pin "1") (pinfunction "1_1") (pintype "unspecified"))
      (node (ref "U1") (pin "49") (pinfunction "PF11_49") (pintype "unspecified"))
    )
    (net (code "45") (name "/TP-2") (class "Default")
      (node (ref "CN5") (pin "1") (pinfunction "1_1") (pintype "unspecified"))
      (node (ref "U1") (pin "50") (pinfunction "PF12_50") (pintype "unspecified"))
    )
    (net (code "46") (name "/TP-3") (class "Default")
      (node (ref "CN7") (pin "1") (pinfunction "1_1") (pintype "unspecified"))
      (node (ref "U1") (pin "59") (pinfunction "PE8_59") (pintype "unspecified"))
    )
    (net (code "47") (name "/TP-4") (class "Default")
      (node (ref "CN6") (pin "1") (pinfunction "1_1") (pintype "unspecified"))
      (node (ref "U1") (pin "60") (pinfunction "PE9_60") (pintype "unspecified"))
    )
    (net (code "48") (name "/TP-5") (class "Default")
      (node (ref "CN9") (pin "1") (pinfunction "1_1") (pintype "unspecified"))
      (node (ref "U1") (pin "63") (pinfunction "PE10_63") (pintype "unspecified"))
    )
    (net (code "49") (name "/TP-6") (class "Default")
      (node (ref "CN8") (pin "1") (pinfunction "1_1") (pintype "unspecified"))
      (node (ref "U1") (pin "64") (pinfunction "PE11_64") (pintype "unspecified"))
    )
    (net (code "50") (name "/nCS") (class "Default")
      (node (ref "R7") (pin "2") (pinfunction "2_2") (pintype "unspecified"))
      (node (ref "U1") (pin "58") (pinfunction "PE7_58") (pintype "unspecified"))
      (node (ref "U3") (pin "22") (pinfunction "nCS_22") (pintype "unspecified"))
    )
    (net (code "51") (name "GND") (class "Default")
      (node (ref "CN1") (pin "1") (pinfunction "1_1") (pintype "unspecified"))
      (node (ref "CN2") (pin "1") (pinfunction "1_1") (pintype "unspecified"))
      (node (ref "J1") (pin "1") (pinfunction "1_1") (pintype "unspecified"))
      (node (ref "R1") (pin "1") (pinfunction "1_1") (pintype "unspecified"))
      (node (ref "R10") (pin "2") (pinfunction "2_2") (pintype "unspecified"))
      (node (ref "R11") (pin "1") (pinfunction "1_1") (pintype "unspecified"))
      (node (ref "R16") (pin "2") (pinfunction "2_2") (pintype "unspecified"))
      (node (ref "R17") (pin "2") (pinfunction "2_2") (pintype "unspecified"))
      (node (ref "R2") (pin "1") (pinfunction "1_1") (pintype "unspecified"))
      (node (ref "R20") (pin "2") (pinfunction "2_2") (pintype "unspecified"))
      (node (ref "R27") (pin "1") (pinfunction "1_1") (pintype "unspecified"))
      (node (ref "R30") (pin "2") (pinfunction "2_2") (pintype "unspecified"))
      (node (ref "R31") (pin "1") (pinfunction "1_1") (pintype "unspecified"))
      (node (ref "R38") (pin "2") (pinfunction "2_2") (pintype "unspecified"))
      (node (ref "R39") (pin "1") (pinfunction "1_1") (pintype "unspecified"))
      (node (ref "R5") (pin "1") (pinfunction "1_1") (pintype "unspecified"))
      (node (ref "R6") (pin "1") (pinfunction "1_1") (pintype "unspecified"))
      (node (ref "U1") (pin "107") (pinfunction "VSS_107") (pintype "unspecified"))
      (node (ref "U1") (pin "120") (pinfunction "VSS_120") (pintype "unspecified"))
      (node (ref "U1") (pin "130") (pinfunction "VSS_130") (pintype "unspecified"))
      (node (ref "U1") (pin "16") (pinfunction "VSS_16") (pintype "unspecified"))
      (node (ref "U1") (pin "38") (pinfunction "VSS_38") (pintype "unspecified"))
      (node (ref "U1") (pin "51") (pinfunction "VSS_51") (pintype "unspecified"))
      (node (ref "U1") (pin "61") (pinfunction "VSS_61") (pintype "unspecified"))
      (node (ref "U1") (pin "83") (pinfunction "VSS_83") (pintype "unspecified"))
      (node (ref "U1") (pin "94") (pinfunction "VSS_94") (pintype "unspecified"))
      (node (ref "U10") (pin "1") (pinfunction "1_1") (pintype "unspecified"))
      (node (ref "U11") (pin "1") (pinfunction "1_1") (pintype "unspecified"))
      (node (ref "U12") (pin "1") (pinfunction "1_1") (pintype "unspecified"))
      (node (ref "U13") (pin "1") (pinfunction "1_1") (pintype "unspecified"))
      (node (ref "U14") (pin "1") (pinfunction "1_1") (pintype "unspecified"))
      (node (ref "U15") (pin "1") (pinfunction "1_1") (pintype "unspecified"))
      (node (ref "U16") (pin "1") (pinfunction "1_1") (pintype "unspecified"))
      (node (ref "U17") (pin "1") (pinfunction "1_1") (pintype "unspecified"))
      (node (ref "U18") (pin "2") (pinfunction "2_2") (pintype "unspecified"))
      (node (ref "U19") (pin "2") (pinfunction "2_2") (pintype "unspecified"))
      (node (ref "U2") (pin "1") (pinfunction "1_1") (pintype "unspecified"))
      (node (ref "U20") (pin "2") (pinfunction "2_2") (pintype "unspecified"))
      (node (ref "U21") (pin "0") (pinfunction "SH_0") (pintype "unspecified"))
      (node (ref "U21") (pin "1") (pinfunction "SH_1") (pintype "unspecified"))
      (node (ref "U21") (pin "2") (pinfunction "SH_2") (pintype "unspecified"))
      (node (ref "U21") (pin "3") (pinfunction "SH_3") (pintype "unspecified"))
      (node (ref "U21") (pin "A1") (pinfunction "GND_A1") (pintype "unspecified"))
      (node (ref "U21") (pin "A12") (pinfunction "GND_A12") (pintype "unspecified"))
      (node (ref "U21") (pin "B1") (pinfunction "GND_B1") (pintype "unspecified"))
      (node (ref "U21") (pin "B12") (pinfunction "GND_B12") (pintype "unspecified"))
      (node (ref "U22") (pin "0") (pinfunction "SH_0") (pintype "unspecified"))
      (node (ref "U22") (pin "1") (pinfunction "SH_1") (pintype "unspecified"))
      (node (ref "U22") (pin "2") (pinfunction "SH_2") (pintype "unspecified"))
      (node (ref "U22") (pin "3") (pinfunction "SH_3") (pintype "unspecified"))
      (node (ref "U22") (pin "A1") (pinfunction "GND_A1") (pintype "unspecified"))
      (node (ref "U22") (pin "A12") (pinfunction "GND_A12") (pintype "unspecified"))
      (node (ref "U22") (pin "B1") (pinfunction "GND_B1") (pintype "unspecified"))
      (node (ref "U22") (pin "B12") (pinfunction "GND_B12") (pintype "unspecified"))
      (node (ref "U23") (pin "1") (pinfunction "ADJ/GND_1") (pintype "passive"))
      (node (ref "U24") (pin "3") (pinfunction "3_3") (pintype "unspecified"))
      (node (ref "U25") (pin "1") (pinfunction "VSS_1") (pintype "unspecified"))
      (node (ref "U26") (pin "3") (pinfunction "3_3") (pintype "unspecified"))
      (node (ref "U27") (pin "3") (pinfunction "3_3") (pintype "unspecified"))
      (node (ref "U28") (pin "2") (pinfunction "2_2") (pintype "unspecified"))
      (node (ref "U29") (pin "2") (pinfunction "2_2") (pintype "unspecified"))
      (node (ref "U3") (pin "18") (pinfunction "GND_18") (pintype "unspecified"))
      (node (ref "U3") (pin "20") (pinfunction "RESV_20") (pintype "unspecified"))
      (node (ref "U30") (pin "2") (pinfunction "2_2") (pintype "unspecified"))
      (node (ref "U31") (pin "2") (pinfunction "2_2") (pintype "unspecified"))
      (node (ref "U32") (pin "1") (pinfunction "GND_1") (pintype "unspecified"))
      (node (ref "U32") (pin "15") (pinfunction "GND_15") (pintype "unspecified"))
      (node (ref "U32") (pin "38") (pinfunction "GND_38") (pintype "unspecified"))
      (node (ref "U32") (pin "39") (pinfunction "GND_39") (pintype "unspecified"))
      (node (ref "U33") (pin "2") (pinfunction "2_2") (pintype "unspecified"))
      (node (ref "U34") (pin "2") (pinfunction "2_2") (pintype "unspecified"))
      (node (ref "U35") (pin "2") (pinfunction "2_2") (pintype "unspecified"))
      (node (ref "U36") (pin "1") (pinfunction "1_1") (pintype "unspecified"))
      (node (ref "U37") (pin "29") (pinfunction "EP_29") (pintype "unspecified"))
      (node (ref "U37") (pin "3") (pinfunction "GND_3") (pintype "unspecified"))
      (node (ref "U39") (pin "1") (pinfunction "1_1") (pintype "unspecified"))
      (node (ref "U4") (pin "1") (pinfunction "1_1") (pintype "unspecified"))
      (node (ref "U40") (pin "1") (pinfunction "1_1") (pintype "unspecified"))
      (node (ref "U5") (pin "1") (pinfunction "1_1") (pintype "unspecified"))
      (node (ref "U6") (pin "1") (pinfunction "1_1") (pintype "unspecified"))
      (node (ref "U7") (pin "1") (pinfunction "1_1") (pintype "unspecified"))
      (node (ref "U8") (pin "1") (pinfunction "1_1") (pintype "unspecified"))
      (node (ref "U9") (pin "1") (pinfunction "1_1") (pintype "unspecified"))
    )
    (net (code "52") (name "Net-(LED1-Pad2)") (class "Default")
      (node (ref "LED1") (pin "2") (pinfunction "2_2") (pintype "unspecified"))
      (node (ref "R15") (pin "1") (pinfunction "1_1") (pintype "unspecified"))
    )
    (net (code "53") (name "Net-(LED2-Pad2)") (class "Default")
      (node (ref "LED2") (pin "2") (pinfunction "2_2") (pintype "unspecified"))
      (node (ref "R16") (pin "1") (pinfunction "1_1") (pintype "unspecified"))
    )
    (net (code "54") (name "Net-(LED3-Pad1)") (class "Default")
      (node (ref "LED3") (pin "1") (pinfunction "1_1") (pintype "unspecified"))
      (node (ref "R18") (pin "2") (pinfunction "2_2") (pintype "unspecified"))
    )
    (net (code "55") (name "Net-(LED3-Pad2)") (class "Default")
      (node (ref "LED3") (pin "2") (pinfunction "2_2") (pintype "unspecified"))
      (node (ref "R17") (pin "1") (pinfunction "1_1") (pintype "unspecified"))
    )
    (net (code "56") (name "Net-(LED4-Pad1)") (class "Default")
      (node (ref "LED4") (pin "1") (pinfunction "1_1") (pintype "unspecified"))
      (node (ref "R19") (pin "2") (pinfunction "2_2") (pintype "unspecified"))
    )
    (net (code "57") (name "Net-(LED4-Pad2)") (class "Default")
      (node (ref "LED4") (pin "2") (pinfunction "2_2") (pintype "unspecified"))
      (node (ref "R20") (pin "1") (pinfunction "1_1") (pintype "unspecified"))
    )
    (net (code "58") (name "Net-(LED5-Pad1)") (class "Default")
      (node (ref "LED5") (pin "1") (pinfunction "1_1") (pintype "unspecified"))
      (node (ref "LED6") (pin "2") (pinfunction "2_2") (pintype "unspecified"))
      (node (ref "R29") (pin "2") (pinfunction "2_2") (pintype "unspecified"))
    )
    (net (code "59") (name "Net-(LED7-Pad2)") (class "Default")
      (node (ref "LED7") (pin "2") (pinfunction "2_2") (pintype "unspecified"))
      (node (ref "LED8") (pin "1") (pinfunction "1_1") (pintype "unspecified"))
      (node (ref "R28") (pin "2") (pinfunction "2_2") (pintype "unspecified"))
    )
    (net (code "60") (name "Net-(LED9-Pad2)") (class "Default")
      (node (ref "LED9") (pin "2") (pinfunction "2_2") (pintype "unspecified"))
      (node (ref "R30") (pin "1") (pinfunction "1_1") (pintype "unspecified"))
    )
    (net (code "61") (name "Net-(LED10-Pad1)") (class "Default")
      (node (ref "LED10") (pin "1") (pinfunction "1_1") (pintype "unspecified"))
      (node (ref "R40") (pin "2") (pinfunction "2_2") (pintype "unspecified"))
    )
    (net (code "62") (name "Net-(LED11-Pad1)") (class "Default")
      (node (ref "LED11") (pin "1") (pinfunction "1_1") (pintype "unspecified"))
      (node (ref "R36") (pin "2") (pinfunction "2_2") (pintype "unspecified"))
    )
    (net (code "63") (name "Net-(R23-Pad1)") (class "Default")
      (node (ref "R23") (pin "1") (pinfunction "1_1") (pintype "unspecified"))
      (node (ref "R35") (pin "1") (pinfunction "1_1") (pintype "unspecified"))
    )
    (net (code "64") (name "Net-(R24-Pad1)") (class "Default")
      (node (ref "R24") (pin "1") (pinfunction "1_1") (pintype "unspecified"))
      (node (ref "R26") (pin "1") (pinfunction "1_1") (pintype "unspecified"))
    )
    (net (code "65") (name "Net-(SW1-B1)") (class "Default")
      (node (ref "R3") (pin "2") (pinfunction "2_2") (pintype "unspecified"))
      (node (ref "SW1") (pin "4") (pinfunction "B1_4") (pintype "input"))
    )
    (net (code "66") (name "Net-(SW1-B2)") (class "Default")
      (node (ref "R4") (pin "2") (pinfunction "2_2") (pintype "unspecified"))
      (node (ref "SW1") (pin "3") (pinfunction "B2_3") (pintype "input"))
    )
    (net (code "67") (name "Net-(U1-PH0)") (class "Default")
      (node (ref "CRYSTAL1") (pin "1") (pinfunction "1_1") (pintype "unspecified"))
      (node (ref "U1") (pin "23") (pinfunction "PH0_23") (pintype "unspecified"))
      (node (ref "U2") (pin "2") (pinfunction "2_2") (pintype "unspecified"))
    )
    (net (code "68") (name "Net-(U1-PH1)") (class "Default")
      (node (ref "CRYSTAL1") (pin "2") (pinfunction "2_2") (pintype "unspecified"))
      (node (ref "U1") (pin "24") (pinfunction "PH1_24") (pintype "unspecified"))
      (node (ref "U4") (pin "2") (pinfunction "2_2") (pintype "unspecified"))
    )
    (net (code "69") (name "Net-(U1-VBAT)") (class "Default")
      (node (ref "U1") (pin "6") (pinfunction "VBAT_6") (pintype "unspecified"))
      (node (ref "U6") (pin "2") (pinfunction "2_2") (pintype "unspecified"))
    )
    (net (code "70") (name "Net-(U1-VCAP_1)") (class "Default")
      (node (ref "U1") (pin "71") (pinfunction "VCAP_1_71") (pintype "unspecified"))
      (node (ref "U10") (pin "2") (pinfunction "2_2") (pintype "unspecified"))
    )
    (net (code "71") (name "Net-(U1-VCAP_2)") (class "Default")
      (node (ref "U1") (pin "106") (pinfunction "VCAP_2_106") (pintype "unspecified"))
      (node (ref "U17") (pin "2") (pinfunction "2_2") (pintype "unspecified"))
    )
    (net (code "72") (name "Net-(U21-CC1)") (class "Default")
      (node (ref "R39") (pin "2") (pinfunction "2_2") (pintype "unspecified"))
      (node (ref "U21") (pin "A5") (pinfunction "CC1_A5") (pintype "unspecified"))
    )
    (net (code "73") (name "Net-(U21-CC2)") (class "Default")
      (node (ref "R38") (pin "1") (pinfunction "1_1") (pintype "unspecified"))
      (node (ref "U21") (pin "B5") (pinfunction "CC2_B5") (pintype "unspecified"))
    )
    (net (code "74") (name "Net-(U22-CC1)") (class "Default")
      (node (ref "R11") (pin "2") (pinfunction "2_2") (pintype "unspecified"))
      (node (ref "U22") (pin "A5") (pinfunction "CC1_A5") (pintype "unspecified"))
    )
    (net (code "75") (name "Net-(U22-CC2)") (class "Default")
      (node (ref "R10") (pin "1") (pinfunction "1_1") (pintype "unspecified"))
      (node (ref "U22") (pin "B5") (pinfunction "CC2_B5") (pintype "unspecified"))
    )
    (net (code "76") (name "Net-(U25-BUSJ)") (class "Default")
      (node (ref "R33") (pin "1") (pinfunction "1_1") (pintype "unspecified"))
      (node (ref "U25") (pin "19") (pinfunction "BUSJ_19") (pintype "unspecified"))
    )
    (net (code "77") (name "Net-(U25-DRV)") (class "Default")
      (node (ref "LED5") (pin "2") (pinfunction "2_2") (pintype "unspecified"))
      (node (ref "LED6") (pin "1") (pinfunction "1_1") (pintype "unspecified"))
      (node (ref "LED7") (pin "1") (pinfunction "1_1") (pintype "unspecified"))
      (node (ref "LED8") (pin "2") (pinfunction "2_2") (pintype "unspecified"))
      (node (ref "LED9") (pin "1") (pinfunction "1_1") (pintype "unspecified"))
      (node (ref "U25") (pin "22") (pinfunction "DRV_22") (pintype "unspecified"))
    )
    (net (code "78") (name "Net-(U25-LED1)") (class "Default")
      (node (ref "R28") (pin "1") (pinfunction "1_1") (pintype "unspecified"))
      (node (ref "U25") (pin "23") (pinfunction "LED1_23") (pintype "unspecified"))
    )
    (net (code "79") (name "Net-(U25-LED2)") (class "Default")
      (node (ref "R29") (pin "1") (pinfunction "1_1") (pintype "unspecified"))
      (node (ref "U25") (pin "24") (pinfunction "LED2_24") (pintype "unspecified"))
    )
    (net (code "80") (name "Net-(U25-REXT)") (class "Default")
      (node (ref "R27") (pin "2") (pinfunction "2_2") (pintype "unspecified"))
      (node (ref "U25") (pin "14") (pinfunction "REXT_14") (pintype "unspecified"))
    )
    (net (code "81") (name "Net-(U25-VBUSM)") (class "Default")
      (node (ref "R31") (pin "2") (pinfunction "2_2") (pintype "unspecified"))
      (node (ref "R32") (pin "1") (pinfunction "1_1") (pintype "unspecified"))
      (node (ref "U25") (pin "18") (pinfunction "VBUSM_18") (pintype "unspecified"))
    )
    (net (code "82") (name "Net-(U25-XIN)") (class "Default")
      (node (ref "CRYSTAL2") (pin "1") (pinfunction "1_1") (pintype "unspecified"))
      (node (ref "U25") (pin "3") (pinfunction "XIN_3") (pintype "unspecified"))
    )
    (net (code "83") (name "Net-(U25-XOUT)") (class "Default")
      (node (ref "CRYSTAL2") (pin "2") (pinfunction "2_2") (pintype "unspecified"))
      (node (ref "U25") (pin "2") (pinfunction "XOUT_2") (pintype "unspecified"))
    )
    (net (code "84") (name "Net-(U25-XRSTJ)") (class "Default")
      (node (ref "R34") (pin "1") (pinfunction "1_1") (pintype "unspecified"))
      (node (ref "U25") (pin "17") (pinfunction "XRSTJ_17") (pintype "unspecified"))
    )
    (net (code "85") (name "Net-(U37-DTR)") (class "Default")
      (node (ref "U37") (pin "28") (pinfunction "DTR_28") (pintype "unspecified"))
      (node (ref "U38") (pin "1") (pinfunction "1_1") (pintype "unspecified"))
    )
    (net (code "86") (name "Net-(U37-RSTb)") (class "Default")
      (node (ref "R37") (pin "1") (pinfunction "1_1") (pintype "unspecified"))
      (node (ref "U37") (pin "9") (pinfunction "RSTb_9") (pintype "unspecified"))
    )
    (net (code "87") (name "Net-(U37-RXD)") (class "Default")
      (node (ref "LED10") (pin "2") (pinfunction "2_2") (pintype "unspecified"))
      (node (ref "R35") (pin "2") (pinfunction "2_2") (pintype "unspecified"))
      (node (ref "U37") (pin "25") (pinfunction "RXD_25") (pintype "unspecified"))
    )
    (net (code "88") (name "Net-(U37-TXD)") (class "Default")
      (node (ref "LED11") (pin "2") (pinfunction "2_2") (pintype "unspecified"))
      (node (ref "R26") (pin "2") (pinfunction "2_2") (pintype "unspecified"))
      (node (ref "U37") (pin "26") (pinfunction "TXD_26") (pintype "unspecified"))
    )
    (net (code "89") (name "Net-(U37-VDD)") (class "Default")
      (node (ref "U36") (pin "2") (pinfunction "2_2") (pintype "unspecified"))
      (node (ref "U37") (pin "6") (pinfunction "VDD_6") (pintype "unspecified"))
    )
    (net (code "90") (name "VCC") (class "Default")
      (node (ref "J1") (pin "4") (pinfunction "4_4") (pintype "unspecified"))
      (node (ref "LED1") (pin "1") (pinfunction "1_1") (pintype "unspecified"))
      (node (ref "LED2") (pin "1") (pinfunction "1_1") (pintype "unspecified"))
      (node (ref "R14") (pin "1") (pinfunction "1_1") (pintype "unspecified"))
      (node (ref "R3") (pin "1") (pinfunction "1_1") (pintype "unspecified"))
      (node (ref "R33") (pin "2") (pinfunction "2_2") (pintype "unspecified"))
      (node (ref "R34") (pin "2") (pinfunction "2_2") (pintype "unspecified"))
      (node (ref "R36") (pin "1") (pinfunction "1_1") (pintype "unspecified"))
      (node (ref "R37") (pin "2") (pinfunction "2_2") (pintype "unspecified"))
      (node (ref "R4") (pin "1") (pinfunction "1_1") (pintype "unspecified"))
      (node (ref "R40") (pin "1") (pinfunction "1_1") (pintype "unspecified"))
      (node (ref "R7") (pin "1") (pinfunction "1_1") (pintype "unspecified"))
      (node (ref "R8") (pin "1") (pinfunction "1_1") (pintype "unspecified"))
      (node (ref "R9") (pin "1") (pinfunction "1_1") (pintype "unspecified"))
      (node (ref "U1") (pin "108") (pinfunction "VDD_108") (pintype "unspecified"))
      (node (ref "U1") (pin "121") (pinfunction "VDD_121") (pintype "unspecified"))
      (node (ref "U1") (pin "131") (pinfunction "VDD_131") (pintype "unspecified"))
      (node (ref "U1") (pin "143") (pinfunction "PDR_ON_143") (pintype "unspecified"))
      (node (ref "U1") (pin "144") (pinfunction "VDD_144") (pintype "unspecified"))
      (node (ref "U1") (pin "17") (pinfunction "VDD_17") (pintype "unspecified"))
      (node (ref "U1") (pin "30") (pinfunction "VDD_30") (pintype "unspecified"))
      (node (ref "U1") (pin "33") (pinfunction "VDDA_33") (pintype "unspecified"))
      (node (ref "U1") (pin "39") (pinfunction "VDD_39") (pintype "unspecified"))
      (node (ref "U1") (pin "52") (pinfunction "VDD_52") (pintype "unspecified"))
      (node (ref "U1") (pin "62") (pinfunction "VDD_62") (pintype "unspecified"))
      (node (ref "U1") (pin "72") (pinfunction "VDD_72") (pintype "unspecified"))
      (node (ref "U1") (pin "84") (pinfunction "VDD_84") (pintype "unspecified"))
      (node (ref "U1") (pin "95") (pinfunction "VDD_95") (pintype "unspecified"))
      (node (ref "U11") (pin "2") (pinfunction "2_2") (pintype "unspecified"))
      (node (ref "U12") (pin "2") (pinfunction "2_2") (pintype "unspecified"))
      (node (ref "U13") (pin "2") (pinfunction "2_2") (pintype "unspecified"))
      (node (ref "U14") (pin "2") (pinfunction "2_2") (pintype "unspecified"))
      (node (ref "U15") (pin "2") (pinfunction "2_2") (pintype "unspecified"))
      (node (ref "U16") (pin "2") (pinfunction "2_2") (pintype "unspecified"))
      (node (ref "U18") (pin "1") (pinfunction "1_1") (pintype "unspecified"))
      (node (ref "U20") (pin "1") (pinfunction "1_1") (pintype "unspecified"))
      (node (ref "U23") (pin "2") (pinfunction "VOUT_2") (pintype "passive"))
      (node (ref "U23") (pin "4") (pinfunction "VOUT_4") (pintype "passive"))
      (node (ref "U25") (pin "13") (pinfunction "VD33_13") (pintype "unspecified"))
      (node (ref "U25") (pin "21") (pinfunction "VD33_O_21") (pintype "unspecified"))
      (node (ref "U25") (pin "26") (pinfunction "OVCJ_26") (pintype "unspecified"))
      (node (ref "U28") (pin "1") (pinfunction "1_1") (pintype "unspecified"))
      (node (ref "U3") (pin "1") (pinfunction "NC_1") (pintype "unspecified"))
      (node (ref "U3") (pin "13") (pinfunction "VDD_13") (pintype "unspecified"))
      (node (ref "U3") (pin "8") (pinfunction "VDDIO_8") (pintype "unspecified"))
      (node (ref "U30") (pin "1") (pinfunction "1_1") (pintype "unspecified"))
      (node (ref "U32") (pin "2") (pinfunction "3V3_2") (pintype "unspecified"))
      (node (ref "U35") (pin "1") (pinfunction "1_1") (pintype "unspecified"))
      (node (ref "U39") (pin "2") (pinfunction "2_2") (pintype "unspecified"))
      (node (ref "U40") (pin "2") (pinfunction "2_2") (pintype "unspecified"))
      (node (ref "U5") (pin "2") (pinfunction "2_2") (pintype "unspecified"))
      (node (ref "U7") (pin "2") (pinfunction "2_2") (pintype "unspecified"))
      (node (ref "U8") (pin "2") (pinfunction "2_2") (pintype "unspecified"))
      (node (ref "U9") (pin "2") (pinfunction "2_2") (pintype "unspecified"))
    )
    (net (code "91") (name "unconnected-(U1-PA0-Pad34)") (class "Default")
      (node (ref "U1") (pin "34") (pinfunction "PA0_34") (pintype "unspecified"))
    )
    (net (code "92") (name "unconnected-(U1-PA1-Pad35)") (class "Default")
      (node (ref "U1") (pin "35") (pinfunction "PA1_35") (pintype "unspecified"))
    )
    (net (code "93") (name "unconnected-(U1-PA2-Pad36)") (class "Default")
      (node (ref "U1") (pin "36") (pinfunction "PA2_36") (pintype "unspecified"))
    )
    (net (code "94") (name "unconnected-(U1-PA5-Pad41)") (class "Default")
      (node (ref "U1") (pin "41") (pinfunction "PA5_41") (pintype "unspecified"))
    )
    (net (code "95") (name "unconnected-(U1-PA6-Pad42)") (class "Default")
      (node (ref "U1") (pin "42") (pinfunction "PA6_42") (pintype "unspecified"))
    )
    (net (code "96") (name "unconnected-(U1-PA7-Pad43)") (class "Default")
      (node (ref "U1") (pin "43") (pinfunction "PA7_43") (pintype "unspecified"))
    )
    (net (code "97") (name "unconnected-(U1-PA8-Pad100)") (class "Default")
      (node (ref "U1") (pin "100") (pinfunction "PA8_100") (pintype "unspecified"))
    )
    (net (code "98") (name "unconnected-(U1-PA9-Pad101)") (class "Default")
      (node (ref "U1") (pin "101") (pinfunction "PA9_101") (pintype "unspecified"))
    )
    (net (code "99") (name "unconnected-(U1-PA10-Pad102)") (class "Default")
      (node (ref "U1") (pin "102") (pinfunction "PA10_102") (pintype "unspecified"))
    )
    (net (code "100") (name "unconnected-(U1-PA15-Pad110)") (class "Default")
      (node (ref "U1") (pin "110") (pinfunction "PA15_110") (pintype "unspecified"))
    )
    (net (code "101") (name "unconnected-(U1-PB0-Pad46)") (class "Default")
      (node (ref "U1") (pin "46") (pinfunction "PB0_46") (pintype "unspecified"))
    )
    (net (code "102") (name "unconnected-(U1-PB1-Pad47)") (class "Default")
      (node (ref "U1") (pin "47") (pinfunction "PB1_47") (pintype "unspecified"))
    )
    (net (code "103") (name "unconnected-(U1-PB3-Pad133)") (class "Default")
      (node (ref "U1") (pin "133") (pinfunction "PB3_133") (pintype "unspecified"))
    )
    (net (code "104") (name "unconnected-(U1-PB4-Pad134)") (class "Default")
      (node (ref "U1") (pin "134") (pinfunction "PB4_134") (pintype "unspecified"))
    )
    (net (code "105") (name "unconnected-(U1-PB5-Pad135)") (class "Default")
      (node (ref "U1") (pin "135") (pinfunction "PB5_135") (pintype "unspecified"))
    )
    (net (code "106") (name "unconnected-(U1-PB8-Pad139)") (class "Default")
      (node (ref "U1") (pin "139") (pinfunction "PB8_139") (pintype "unspecified"))
    )
    (net (code "107") (name "unconnected-(U1-PB9-Pad140)") (class "Default")
      (node (ref "U1") (pin "140") (pinfunction "PB9_140") (pintype "unspecified"))
    )
    (net (code "108") (name "unconnected-(U1-PB10-Pad69)") (class "Default")
      (node (ref "U1") (pin "69") (pinfunction "PB10_69") (pintype "unspecified"))
    )
    (net (code "109") (name "unconnected-(U1-PB11-Pad70)") (class "Default")
      (node (ref "U1") (pin "70") (pinfunction "PB11_70") (pintype "unspecified"))
    )
    (net (code "110") (name "unconnected-(U1-PB12-Pad73)") (class "Default")
      (node (ref "U1") (pin "73") (pinfunction "PB12_73") (pintype "unspecified"))
    )
    (net (code "111") (name "unconnected-(U1-PB13-Pad74)") (class "Default")
      (node (ref "U1") (pin "74") (pinfunction "PB13_74") (pintype "unspecified"))
    )
    (net (code "112") (name "unconnected-(U1-PB14-Pad75)") (class "Default")
      (node (ref "U1") (pin "75") (pinfunction "PB14_75") (pintype "unspecified"))
    )
    (net (code "113") (name "unconnected-(U1-PB15-Pad76)") (class "Default")
      (node (ref "U1") (pin "76") (pinfunction "PB15_76") (pintype "unspecified"))
    )
    (net (code "114") (name "unconnected-(U1-PC0-Pad26)") (class "Default")
      (node (ref "U1") (pin "26") (pinfunction "PC0_26") (pintype "unspecified"))
    )
    (net (code "115") (name "unconnected-(U1-PC1-Pad27)") (class "Default")
      (node (ref "U1") (pin "27") (pinfunction "PC1_27") (pintype "unspecified"))
    )
    (net (code "116") (name "unconnected-(U1-PC2-Pad28)") (class "Default")
      (node (ref "U1") (pin "28") (pinfunction "PC2_28") (pintype "unspecified"))
    )
    (net (code "117") (name "unconnected-(U1-PC3-Pad29)") (class "Default")
      (node (ref "U1") (pin "29") (pinfunction "PC3_29") (pintype "unspecified"))
    )
    (net (code "118") (name "unconnected-(U1-PC4-Pad44)") (class "Default")
      (node (ref "U1") (pin "44") (pinfunction "PC4_44") (pintype "unspecified"))
    )
    (net (code "119") (name "unconnected-(U1-PC5-Pad45)") (class "Default")
      (node (ref "U1") (pin "45") (pinfunction "PC5_45") (pintype "unspecified"))
    )
    (net (code "120") (name "unconnected-(U1-PC6-Pad96)") (class "Default")
      (node (ref "U1") (pin "96") (pinfunction "PC6_96") (pintype "unspecified"))
    )
    (net (code "121") (name "unconnected-(U1-PC7-Pad97)") (class "Default")
      (node (ref "U1") (pin "97") (pinfunction "PC7_97") (pintype "unspecified"))
    )
    (net (code "122") (name "unconnected-(U1-PC8-Pad98)") (class "Default")
      (node (ref "U1") (pin "98") (pinfunction "PC8_98") (pintype "unspecified"))
    )
    (net (code "123") (name "unconnected-(U1-PC9-Pad99)") (class "Default")
      (node (ref "U1") (pin "99") (pinfunction "PC9_99") (pintype "unspecified"))
    )
    (net (code "124") (name "unconnected-(U1-PC13-Pad7)") (class "Default")
      (node (ref "U1") (pin "7") (pinfunction "PC13_7") (pintype "unspecified"))
    )
    (net (code "125") (name "unconnected-(U1-PC14-Pad8)") (class "Default")
      (node (ref "U1") (pin "8") (pinfunction "PC14_8") (pintype "unspecified"))
    )
    (net (code "126") (name "unconnected-(U1-PC15-Pad9)") (class "Default")
      (node (ref "U1") (pin "9") (pinfunction "PC15_9") (pintype "unspecified"))
    )
    (net (code "127") (name "unconnected-(U1-PD0-Pad114)") (class "Default")
      (node (ref "U1") (pin "114") (pinfunction "PD0_114") (pintype "unspecified"))
    )
    (net (code "128") (name "unconnected-(U1-PD1-Pad115)") (class "Default")
      (node (ref "U1") (pin "115") (pinfunction "PD1_115") (pintype "unspecified"))
    )
    (net (code "129") (name "unconnected-(U1-PD3-Pad117)") (class "Default")
      (node (ref "U1") (pin "117") (pinfunction "PD3_117") (pintype "unspecified"))
    )
    (net (code "130") (name "unconnected-(U1-PD4-Pad118)") (class "Default")
      (node (ref "U1") (pin "118") (pinfunction "PD4_118") (pintype "unspecified"))
    )
    (net (code "131") (name "unconnected-(U1-PD5-Pad119)") (class "Default")
      (node (ref "U1") (pin "119") (pinfunction "PD5_119") (pintype "unspecified"))
    )
    (net (code "132") (name "unconnected-(U1-PD6-Pad122)") (class "Default")
      (node (ref "U1") (pin "122") (pinfunction "PD6_122") (pintype "unspecified"))
    )
    (net (code "133") (name "unconnected-(U1-PD7-Pad123)") (class "Default")
      (node (ref "U1") (pin "123") (pinfunction "PD7_123") (pintype "unspecified"))
    )
    (net (code "134") (name "unconnected-(U1-PD8-Pad77)") (class "Default")
      (node (ref "U1") (pin "77") (pinfunction "PD8_77") (pintype "unspecified"))
    )
    (net (code "135") (name "unconnected-(U1-PD9-Pad78)") (class "Default")
      (node (ref "U1") (pin "78") (pinfunction "PD9_78") (pintype "unspecified"))
    )
    (net (code "136") (name "unconnected-(U1-PD10-Pad79)") (class "Default")
      (node (ref "U1") (pin "79") (pinfunction "PD10_79") (pintype "unspecified"))
    )
    (net (code "137") (name "unconnected-(U1-PD11-Pad80)") (class "Default")
      (node (ref "U1") (pin "80") (pinfunction "PD11_80") (pintype "unspecified"))
    )
    (net (code "138") (name "unconnected-(U1-PD12-Pad81)") (class "Default")
      (node (ref "U1") (pin "81") (pinfunction "PD12_81") (pintype "unspecified"))
    )
    (net (code "139") (name "unconnected-(U1-PD13-Pad82)") (class "Default")
      (node (ref "U1") (pin "82") (pinfunction "PD13_82") (pintype "unspecified"))
    )
    (net (code "140") (name "unconnected-(U1-PD14-Pad85)") (class "Default")
      (node (ref "U1") (pin "85") (pinfunction "PD14_85") (pintype "unspecified"))
    )
    (net (code "141") (name "unconnected-(U1-PD15-Pad86)") (class "Default")
      (node (ref "U1") (pin "86") (pinfunction "PD15_86") (pintype "unspecified"))
    )
    (net (code "142") (name "unconnected-(U1-PE0-Pad141)") (class "Default")
      (node (ref "U1") (pin "141") (pinfunction "PE0_141") (pintype "unspecified"))
    )
    (net (code "143") (name "unconnected-(U1-PE1-Pad142)") (class "Default")
      (node (ref "U1") (pin "142") (pinfunction "PE1_142") (pintype "unspecified"))
    )
    (net (code "144") (name "unconnected-(U1-PE2-Pad1)") (class "Default")
      (node (ref "U1") (pin "1") (pinfunction "PE2_1") (pintype "unspecified"))
    )
    (net (code "145") (name "unconnected-(U1-PE3-Pad2)") (class "Default")
      (node (ref "U1") (pin "2") (pinfunction "PE3_2") (pintype "unspecified"))
    )
    (net (code "146") (name "unconnected-(U1-PE4-Pad3)") (class "Default")
      (node (ref "U1") (pin "3") (pinfunction "PE4_3") (pintype "unspecified"))
    )
    (net (code "147") (name "unconnected-(U1-PE5-Pad4)") (class "Default")
      (node (ref "U1") (pin "4") (pinfunction "PE5_4") (pintype "unspecified"))
    )
    (net (code "148") (name "unconnected-(U1-PE6-Pad5)") (class "Default")
      (node (ref "U1") (pin "5") (pinfunction "PE6_5") (pintype "unspecified"))
    )
    (net (code "149") (name "unconnected-(U1-PE12-Pad65)") (class "Default")
      (node (ref "U1") (pin "65") (pinfunction "PE12_65") (pintype "unspecified"))
    )
    (net (code "150") (name "unconnected-(U1-PE13-Pad66)") (class "Default")
      (node (ref "U1") (pin "66") (pinfunction "PE13_66") (pintype "unspecified"))
    )
    (net (code "151") (name "unconnected-(U1-PE14-Pad67)") (class "Default")
      (node (ref "U1") (pin "67") (pinfunction "PE14_67") (pintype "unspecified"))
    )
    (net (code "152") (name "unconnected-(U1-PE15-Pad68)") (class "Default")
      (node (ref "U1") (pin "68") (pinfunction "PE15_68") (pintype "unspecified"))
    )
    (net (code "153") (name "unconnected-(U1-PF2-Pad12)") (class "Default")
      (node (ref "U1") (pin "12") (pinfunction "PF2_12") (pintype "unspecified"))
    )
    (net (code "154") (name "unconnected-(U1-PF3-Pad13)") (class "Default")
      (node (ref "U1") (pin "13") (pinfunction "PF3_13") (pintype "unspecified"))
    )
    (net (code "155") (name "unconnected-(U1-PF4-Pad14)") (class "Default")
      (node (ref "U1") (pin "14") (pinfunction "PF4_14") (pintype "unspecified"))
    )
    (net (code "156") (name "unconnected-(U1-PF5-Pad15)") (class "Default")
      (node (ref "U1") (pin "15") (pinfunction "PF5_15") (pintype "unspecified"))
    )
    (net (code "157") (name "unconnected-(U1-PF6-Pad18)") (class "Default")
      (node (ref "U1") (pin "18") (pinfunction "PF6_18") (pintype "unspecified"))
    )
    (net (code "158") (name "unconnected-(U1-PF7-Pad19)") (class "Default")
      (node (ref "U1") (pin "19") (pinfunction "PF7_19") (pintype "unspecified"))
    )
    (net (code "159") (name "unconnected-(U1-PF8-Pad20)") (class "Default")
      (node (ref "U1") (pin "20") (pinfunction "PF8_20") (pintype "unspecified"))
    )
    (net (code "160") (name "unconnected-(U1-PF9-Pad21)") (class "Default")
      (node (ref "U1") (pin "21") (pinfunction "PF9_21") (pintype "unspecified"))
    )
    (net (code "161") (name "unconnected-(U1-PF10-Pad22)") (class "Default")
      (node (ref "U1") (pin "22") (pinfunction "PF10_22") (pintype "unspecified"))
    )
    (net (code "162") (name "unconnected-(U1-PG2-Pad87)") (class "Default")
      (node (ref "U1") (pin "87") (pinfunction "PG2_87") (pintype "unspecified"))
    )
    (net (code "163") (name "unconnected-(U1-PG3-Pad88)") (class "Default")
      (node (ref "U1") (pin "88") (pinfunction "PG3_88") (pintype "unspecified"))
    )
    (net (code "164") (name "unconnected-(U1-PG4-Pad89)") (class "Default")
      (node (ref "U1") (pin "89") (pinfunction "PG4_89") (pintype "unspecified"))
    )
    (net (code "165") (name "unconnected-(U1-PG5-Pad90)") (class "Default")
      (node (ref "U1") (pin "90") (pinfunction "PG5_90") (pintype "unspecified"))
    )
    (net (code "166") (name "unconnected-(U1-PG6-Pad91)") (class "Default")
      (node (ref "U1") (pin "91") (pinfunction "PG6_91") (pintype "unspecified"))
    )
    (net (code "167") (name "unconnected-(U1-PG7-Pad92)") (class "Default")
      (node (ref "U1") (pin "92") (pinfunction "PG7_92") (pintype "unspecified"))
    )
    (net (code "168") (name "unconnected-(U1-PG8-Pad93)") (class "Default")
      (node (ref "U1") (pin "93") (pinfunction "PG8_93") (pintype "unspecified"))
    )
    (net (code "169") (name "unconnected-(U1-PG9-Pad124)") (class "Default")
      (node (ref "U1") (pin "124") (pinfunction "PG9_124") (pintype "unspecified"))
    )
    (net (code "170") (name "unconnected-(U1-PG10-Pad125)") (class "Default")
      (node (ref "U1") (pin "125") (pinfunction "PG10_125") (pintype "unspecified"))
    )
    (net (code "171") (name "unconnected-(U1-PG11-Pad126)") (class "Default")
      (node (ref "U1") (pin "126") (pinfunction "PG11_126") (pintype "unspecified"))
    )
    (net (code "172") (name "unconnected-(U1-PG12-Pad127)") (class "Default")
      (node (ref "U1") (pin "127") (pinfunction "PG12_127") (pintype "unspecified"))
    )
    (net (code "173") (name "unconnected-(U1-PG13-Pad128)") (class "Default")
      (node (ref "U1") (pin "128") (pinfunction "PG13_128") (pintype "unspecified"))
    )
    (net (code "174") (name "unconnected-(U1-PG14-Pad129)") (class "Default")
      (node (ref "U1") (pin "129") (pinfunction "PG14_129") (pintype "unspecified"))
    )
    (net (code "175") (name "unconnected-(U1-VREF+-Pad32)") (class "Default")
      (node (ref "U1") (pin "32") (pinfunction "VREF+_32") (pintype "unspecified"))
    )
    (net (code "176") (name "unconnected-(U1-VSSA-Pad31)") (class "Default")
      (node (ref "U1") (pin "31") (pinfunction "VSSA_31") (pintype "unspecified"))
    )
    (net (code "177") (name "unconnected-(U3-EP-Pad25)") (class "Default")
      (node (ref "U3") (pin "25") (pinfunction "EP_25") (pintype "unspecified"))
    )
    (net (code "178") (name "unconnected-(U3-NC-Pad2)") (class "Default")
      (node (ref "U3") (pin "2") (pinfunction "NC_2") (pintype "unspecified"))
    )
    (net (code "179") (name "unconnected-(U3-NC-Pad3)") (class "Default")
      (node (ref "U3") (pin "3") (pinfunction "NC_3") (pintype "unspecified"))
    )
    (net (code "180") (name "unconnected-(U3-NC-Pad4)") (class "Default")
      (node (ref "U3") (pin "4") (pinfunction "NC_4") (pintype "unspecified"))
    )
    (net (code "181") (name "unconnected-(U3-NC-Pad5)") (class "Default")
      (node (ref "U3") (pin "5") (pinfunction "NC_5") (pintype "unspecified"))
    )
    (net (code "182") (name "unconnected-(U3-NC-Pad6)") (class "Default")
      (node (ref "U3") (pin "6") (pinfunction "NC_6") (pintype "unspecified"))
    )
    (net (code "183") (name "unconnected-(U3-NC-Pad14)") (class "Default")
      (node (ref "U3") (pin "14") (pinfunction "NC_14") (pintype "unspecified"))
    )
    (net (code "184") (name "unconnected-(U3-NC-Pad15)") (class "Default")
      (node (ref "U3") (pin "15") (pinfunction "NC_15") (pintype "unspecified"))
    )
    (net (code "185") (name "unconnected-(U3-NC-Pad16)") (class "Default")
      (node (ref "U3") (pin "16") (pinfunction "NC_16") (pintype "unspecified"))
    )
    (net (code "186") (name "unconnected-(U3-NC-Pad17)") (class "Default")
      (node (ref "U3") (pin "17") (pinfunction "NC_17") (pintype "unspecified"))
    )
    (net (code "187") (name "unconnected-(U3-RESV-Pad19)") (class "Default")
      (node (ref "U3") (pin "19") (pinfunction "RESV_19") (pintype "unspecified"))
    )
    (net (code "188") (name "unconnected-(U21-SBU1-PadA8)") (class "Default")
      (node (ref "U21") (pin "A8") (pinfunction "SBU1_A8") (pintype "unspecified"))
    )
    (net (code "189") (name "unconnected-(U21-SBU2-PadB8)") (class "Default")
      (node (ref "U21") (pin "B8") (pinfunction "SBU2_B8") (pintype "unspecified"))
    )
    (net (code "190") (name "unconnected-(U22-SBU1-PadA8)") (class "Default")
      (node (ref "U22") (pin "A8") (pinfunction "SBU1_A8") (pintype "unspecified"))
    )
    (net (code "191") (name "unconnected-(U22-SBU2-PadB8)") (class "Default")
      (node (ref "U22") (pin "B8") (pinfunction "SBU2_B8") (pintype "unspecified"))
    )
    (net (code "192") (name "unconnected-(U24-Pad1)") (class "Default")
      (node (ref "U24") (pin "1") (pinfunction "1_1") (pintype "unspecified"))
    )
    (net (code "193") (name "unconnected-(U24-Pad4)") (class "Default")
      (node (ref "U24") (pin "4") (pinfunction "4_4") (pintype "unspecified"))
    )
    (net (code "194") (name "unconnected-(U25-PWRJ-Pad25)") (class "Default")
      (node (ref "U25") (pin "25") (pinfunction "PWRJ_25") (pintype "unspecified"))
    )
    (net (code "195") (name "unconnected-(U25-TESTJ-Pad27)") (class "Default")
      (node (ref "U25") (pin "27") (pinfunction "TESTJ_27") (pintype "unspecified"))
    )
    (net (code "196") (name "unconnected-(U26-Pad1)") (class "Default")
      (node (ref "U26") (pin "1") (pinfunction "1_1") (pintype "unspecified"))
    )
    (net (code "197") (name "unconnected-(U26-Pad4)") (class "Default")
      (node (ref "U26") (pin "4") (pinfunction "4_4") (pintype "unspecified"))
    )
    (net (code "198") (name "unconnected-(U27-Pad1)") (class "Default")
      (node (ref "U27") (pin "1") (pinfunction "1_1") (pintype "unspecified"))
    )
    (net (code "199") (name "unconnected-(U27-Pad4)") (class "Default")
      (node (ref "U27") (pin "4") (pinfunction "4_4") (pintype "unspecified"))
    )
    (net (code "200") (name "unconnected-(U32-IO5-Pad29)") (class "Default")
      (node (ref "U32") (pin "29") (pinfunction "IO5_29") (pintype "unspecified"))
    )
    (net (code "201") (name "unconnected-(U32-IO12-Pad14)") (class "Default")
      (node (ref "U32") (pin "14") (pinfunction "IO12_14") (pintype "unspecified"))
    )
    (net (code "202") (name "unconnected-(U32-IO13-Pad16)") (class "Default")
      (node (ref "U32") (pin "16") (pinfunction "IO13_16") (pintype "unspecified"))
    )
    (net (code "203") (name "unconnected-(U32-IO14-Pad13)") (class "Default")
      (node (ref "U32") (pin "13") (pinfunction "IO14_13") (pintype "unspecified"))
    )
    (net (code "204") (name "unconnected-(U32-IO15-Pad23)") (class "Default")
      (node (ref "U32") (pin "23") (pinfunction "IO15_23") (pintype "unspecified"))
    )
    (net (code "205") (name "unconnected-(U32-IO16-Pad27)") (class "Default")
      (node (ref "U32") (pin "27") (pinfunction "IO16_27") (pintype "unspecified"))
    )
    (net (code "206") (name "unconnected-(U32-IO17-Pad28)") (class "Default")
      (node (ref "U32") (pin "28") (pinfunction "IO17_28") (pintype "unspecified"))
    )
    (net (code "207") (name "unconnected-(U32-IO18-Pad30)") (class "Default")
      (node (ref "U32") (pin "30") (pinfunction "IO18_30") (pintype "unspecified"))
    )
    (net (code "208") (name "unconnected-(U32-IO19-Pad31)") (class "Default")
      (node (ref "U32") (pin "31") (pinfunction "IO19_31") (pintype "unspecified"))
    )
    (net (code "209") (name "unconnected-(U32-IO23-Pad37)") (class "Default")
      (node (ref "U32") (pin "37") (pinfunction "IO23_37") (pintype "unspecified"))
    )
    (net (code "210") (name "unconnected-(U32-IO25-Pad10)") (class "Default")
      (node (ref "U32") (pin "10") (pinfunction "IO25_10") (pintype "unspecified"))
    )
    (net (code "211") (name "unconnected-(U32-IO26-Pad11)") (class "Default")
      (node (ref "U32") (pin "11") (pinfunction "IO26_11") (pintype "unspecified"))
    )
    (net (code "212") (name "unconnected-(U32-IO27-Pad12)") (class "Default")
      (node (ref "U32") (pin "12") (pinfunction "IO27_12") (pintype "unspecified"))
    )
    (net (code "213") (name "unconnected-(U32-IO32-Pad8)") (class "Default")
      (node (ref "U32") (pin "8") (pinfunction "IO32_8") (pintype "unspecified"))
    )
    (net (code "214") (name "unconnected-(U32-IO33-Pad9)") (class "Default")
      (node (ref "U32") (pin "9") (pinfunction "IO33_9") (pintype "unspecified"))
    )
    (net (code "215") (name "unconnected-(U32-NC-Pad32)") (class "Default")
      (node (ref "U32") (pin "32") (pinfunction "NC_32") (pintype "unspecified"))
    )
    (net (code "216") (name "unconnected-(U32-SCK{slash}CLK-Pad20)") (class "Default")
      (node (ref "U32") (pin "20") (pinfunction "SCK/CLK_20") (pintype "unspecified"))
    )
    (net (code "217") (name "unconnected-(U32-SCS{slash}CMD-Pad19)") (class "Default")
      (node (ref "U32") (pin "19") (pinfunction "SCS/CMD_19") (pintype "unspecified"))
    )
    (net (code "218") (name "unconnected-(U32-SDI{slash}SD1-Pad22)") (class "Default")
      (node (ref "U32") (pin "22") (pinfunction "SDI/SD1_22") (pintype "unspecified"))
    )
    (net (code "219") (name "unconnected-(U32-SDO{slash}SD0-Pad21)") (class "Default")
      (node (ref "U32") (pin "21") (pinfunction "SDO/SD0_21") (pintype "unspecified"))
    )
    (net (code "220") (name "unconnected-(U32-SENSOR_VN-Pad5)") (class "Default")
      (node (ref "U32") (pin "5") (pinfunction "SENSOR_VN_5") (pintype "unspecified"))
    )
    (net (code "221") (name "unconnected-(U32-SENSOR_VP-Pad4)") (class "Default")
      (node (ref "U32") (pin "4") (pinfunction "SENSOR_VP_4") (pintype "unspecified"))
    )
    (net (code "222") (name "unconnected-(U32-SHD{slash}SD2-Pad17)") (class "Default")
      (node (ref "U32") (pin "17") (pinfunction "SHD/SD2_17") (pintype "unspecified"))
    )
    (net (code "223") (name "unconnected-(U32-SWP{slash}SD3-Pad18)") (class "Default")
      (node (ref "U32") (pin "18") (pinfunction "SWP/SD3_18") (pintype "unspecified"))
    )
    (net (code "224") (name "unconnected-(U37-CHR0-Pad15)") (class "Default")
      (node (ref "U37") (pin "15") (pinfunction "CHR0_15") (pintype "unspecified"))
    )
    (net (code "225") (name "unconnected-(U37-CHR1-Pad14)") (class "Default")
      (node (ref "U37") (pin "14") (pinfunction "CHR1_14") (pintype "unspecified"))
    )
    (net (code "226") (name "unconnected-(U37-CHREN-Pad13)") (class "Default")
      (node (ref "U37") (pin "13") (pinfunction "CHREN_13") (pintype "unspecified"))
    )
    (net (code "227") (name "unconnected-(U37-CTS-Pad23)") (class "Default")
      (node (ref "U37") (pin "23") (pinfunction "CTS_23") (pintype "unspecified"))
    )
    (net (code "228") (name "unconnected-(U37-DCD-Pad1)") (class "Default")
      (node (ref "U37") (pin "1") (pinfunction "DCD_1") (pintype "unspecified"))
    )
    (net (code "229") (name "unconnected-(U37-DSR-Pad27)") (class "Default")
      (node (ref "U37") (pin "27") (pinfunction "DSR_27") (pintype "unspecified"))
    )
    (net (code "230") (name "unconnected-(U37-GPIO.0{slash}TXT-Pad19)") (class "Default")
      (node (ref "U37") (pin "19") (pinfunction "GPIO.0/TXT_19") (pintype "unspecified"))
    )
    (net (code "231") (name "unconnected-(U37-GPIO.1{slash}RXT-Pad18)") (class "Default")
      (node (ref "U37") (pin "18") (pinfunction "GPIO.1/RXT_18") (pintype "unspecified"))
    )
    (net (code "232") (name "unconnected-(U37-GPIO.2{slash}RS485-Pad17)") (class "Default")
      (node (ref "U37") (pin "17") (pinfunction "GPIO.2/RS485_17") (pintype "unspecified"))
    )
    (net (code "233") (name "unconnected-(U37-GPIO.3{slash}WAKEUP-Pad16)") (class "Default")
      (node (ref "U37") (pin "16") (pinfunction "GPIO.3/WAKEUP_16") (pintype "unspecified"))
    )
    (net (code "234") (name "unconnected-(U37-GPIO.4-Pad22)") (class "Default")
      (node (ref "U37") (pin "22") (pinfunction "GPIO.4_22") (pintype "unspecified"))
    )
    (net (code "235") (name "unconnected-(U37-GPIO.5-Pad21)") (class "Default")
      (node (ref "U37") (pin "21") (pinfunction "GPIO.5_21") (pintype "unspecified"))
    )
    (net (code "236") (name "unconnected-(U37-GPIO.6-Pad20)") (class "Default")
      (node (ref "U37") (pin "20") (pinfunction "GPIO.6_20") (pintype "unspecified"))
    )
    (net (code "237") (name "unconnected-(U37-NC-Pad10)") (class "Default")
      (node (ref "U37") (pin "10") (pinfunction "NC_10") (pintype "unspecified"))
    )
    (net (code "238") (name "unconnected-(U37-RI{slash}CLK-Pad2)") (class "Default")
      (node (ref "U37") (pin "2") (pinfunction "RI/CLK_2") (pintype "unspecified"))
    )
    (net (code "239") (name "unconnected-(U37-RTS-Pad24)") (class "Default")
      (node (ref "U37") (pin "24") (pinfunction "RTS_24") (pintype "unspecified"))
    )
    (net (code "240") (name "unconnected-(U37-SUSPEND-Pad12)") (class "Default")
      (node (ref "U37") (pin "12") (pinfunction "SUSPEND_12") (pintype "unspecified"))
    )
    (net (code "241") (name "unconnected-(U37-SUSPENDb-Pad11)") (class "Default")
      (node (ref "U37") (pin "11") (pinfunction "SUSPENDb_11") (pintype "unspecified"))
    )
  )
)
